# FlatSat_Final.net
KiCad netlist of a schematic drawn in EAGLE
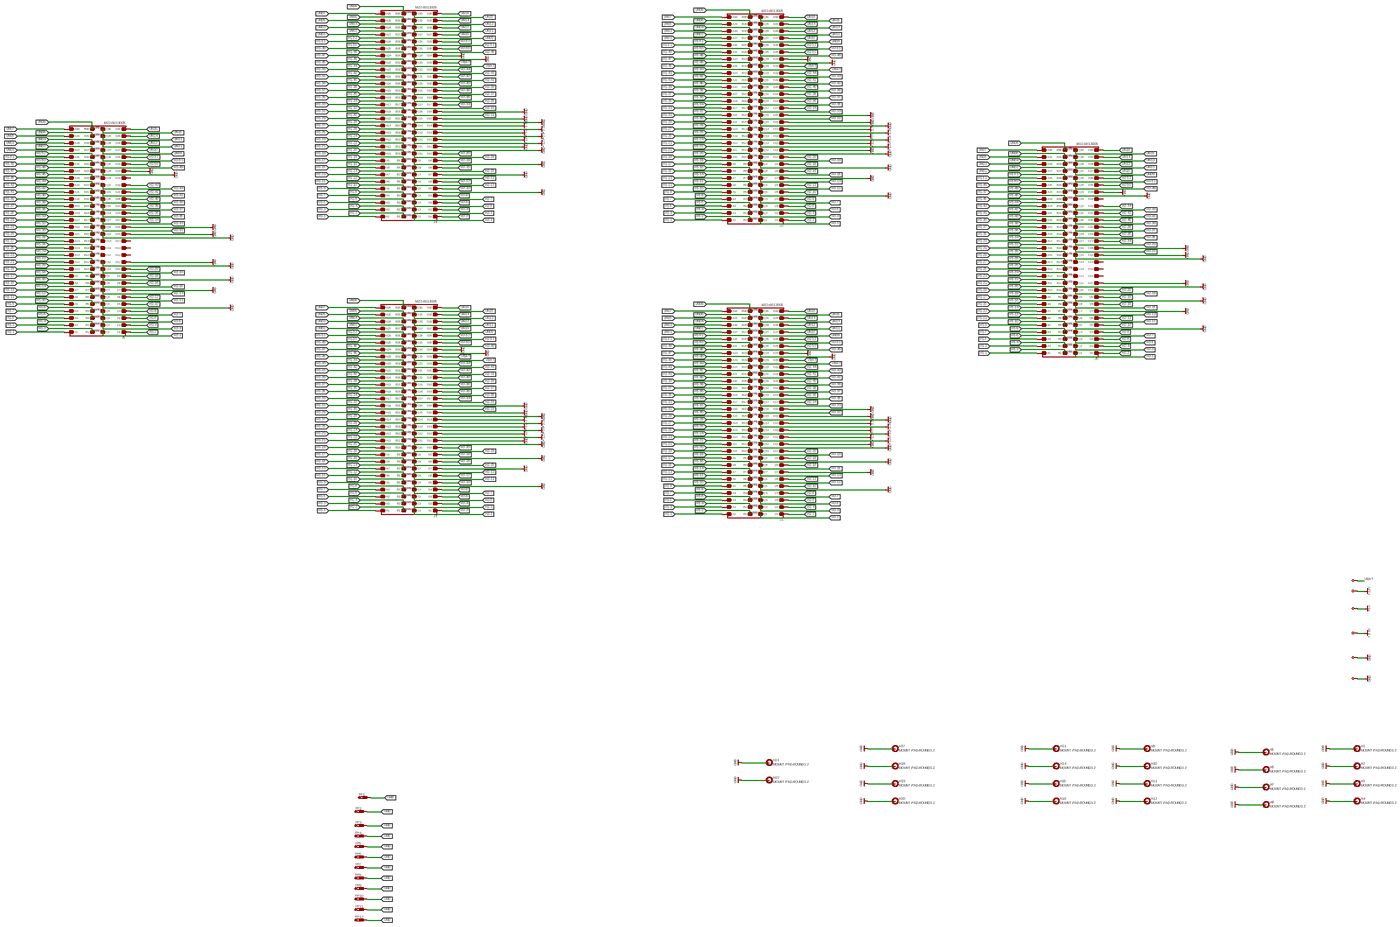
[diagram p0: schematic, sheet 1, overview]
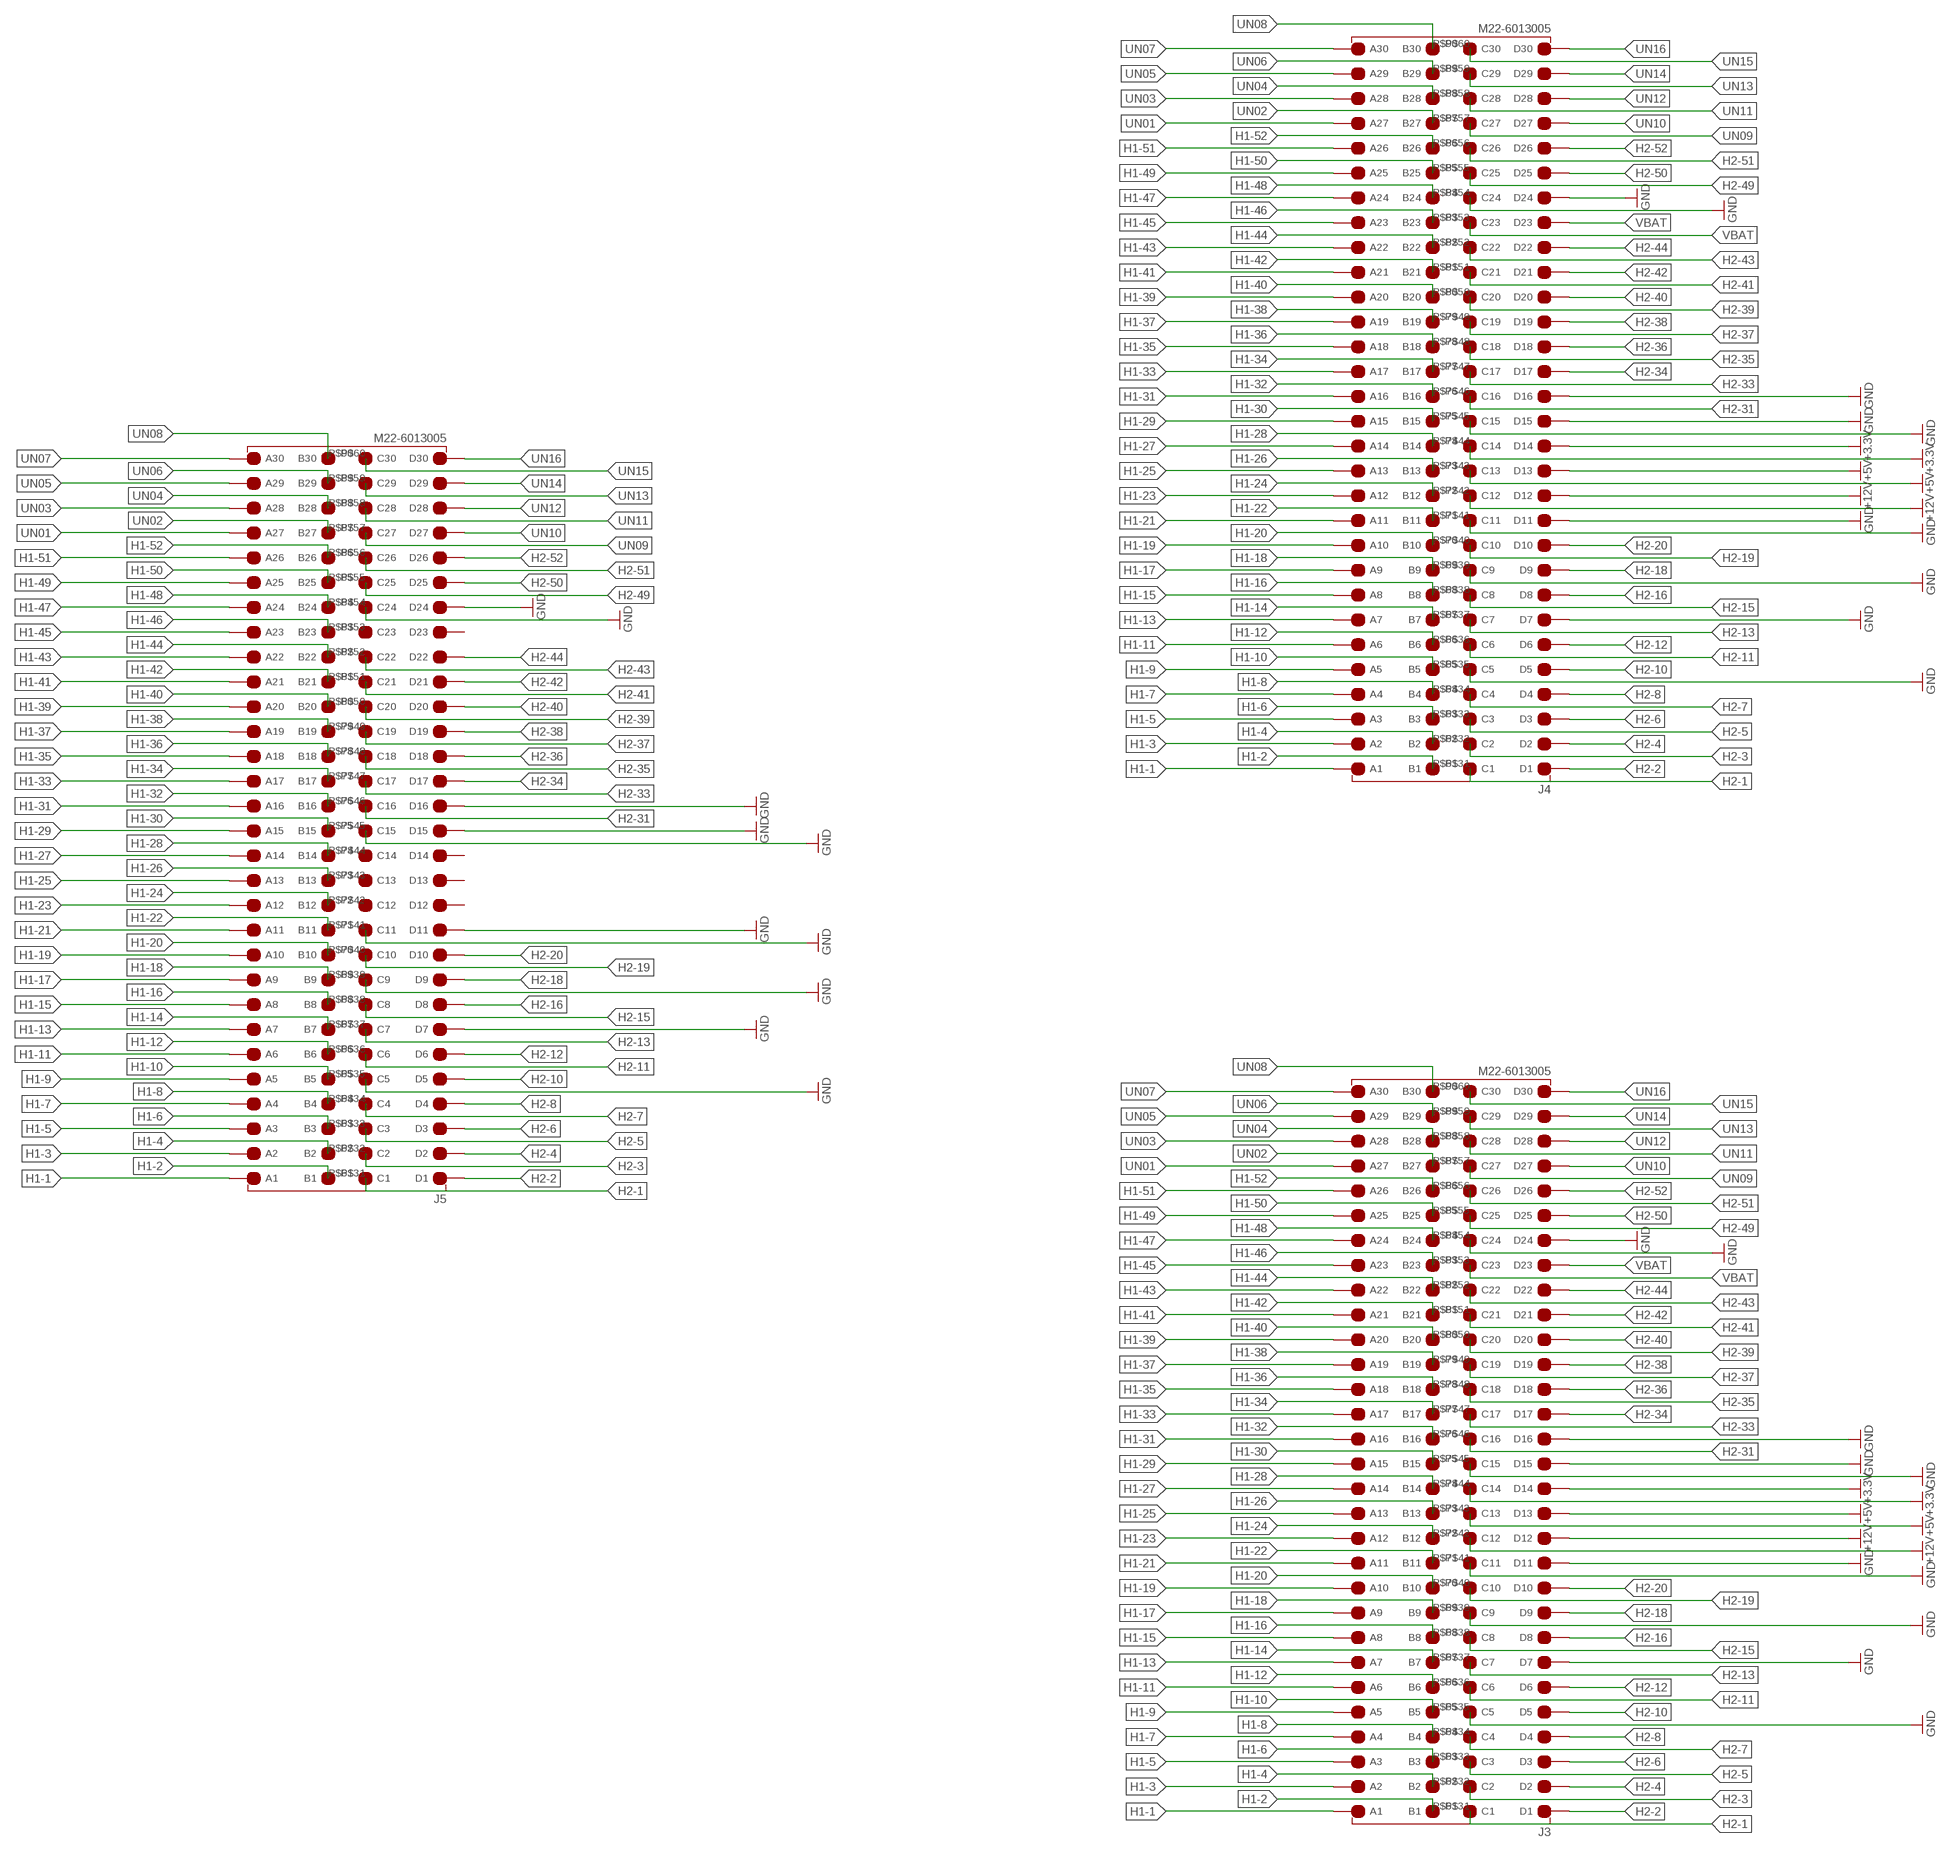
[diagram p1: schematic, sheet 1, part 1 of 5]
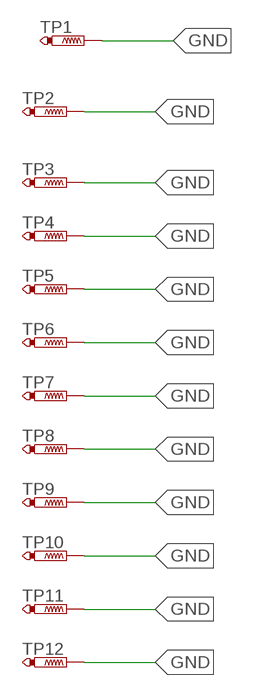
[diagram p2: schematic, sheet 1, part 2 of 5]
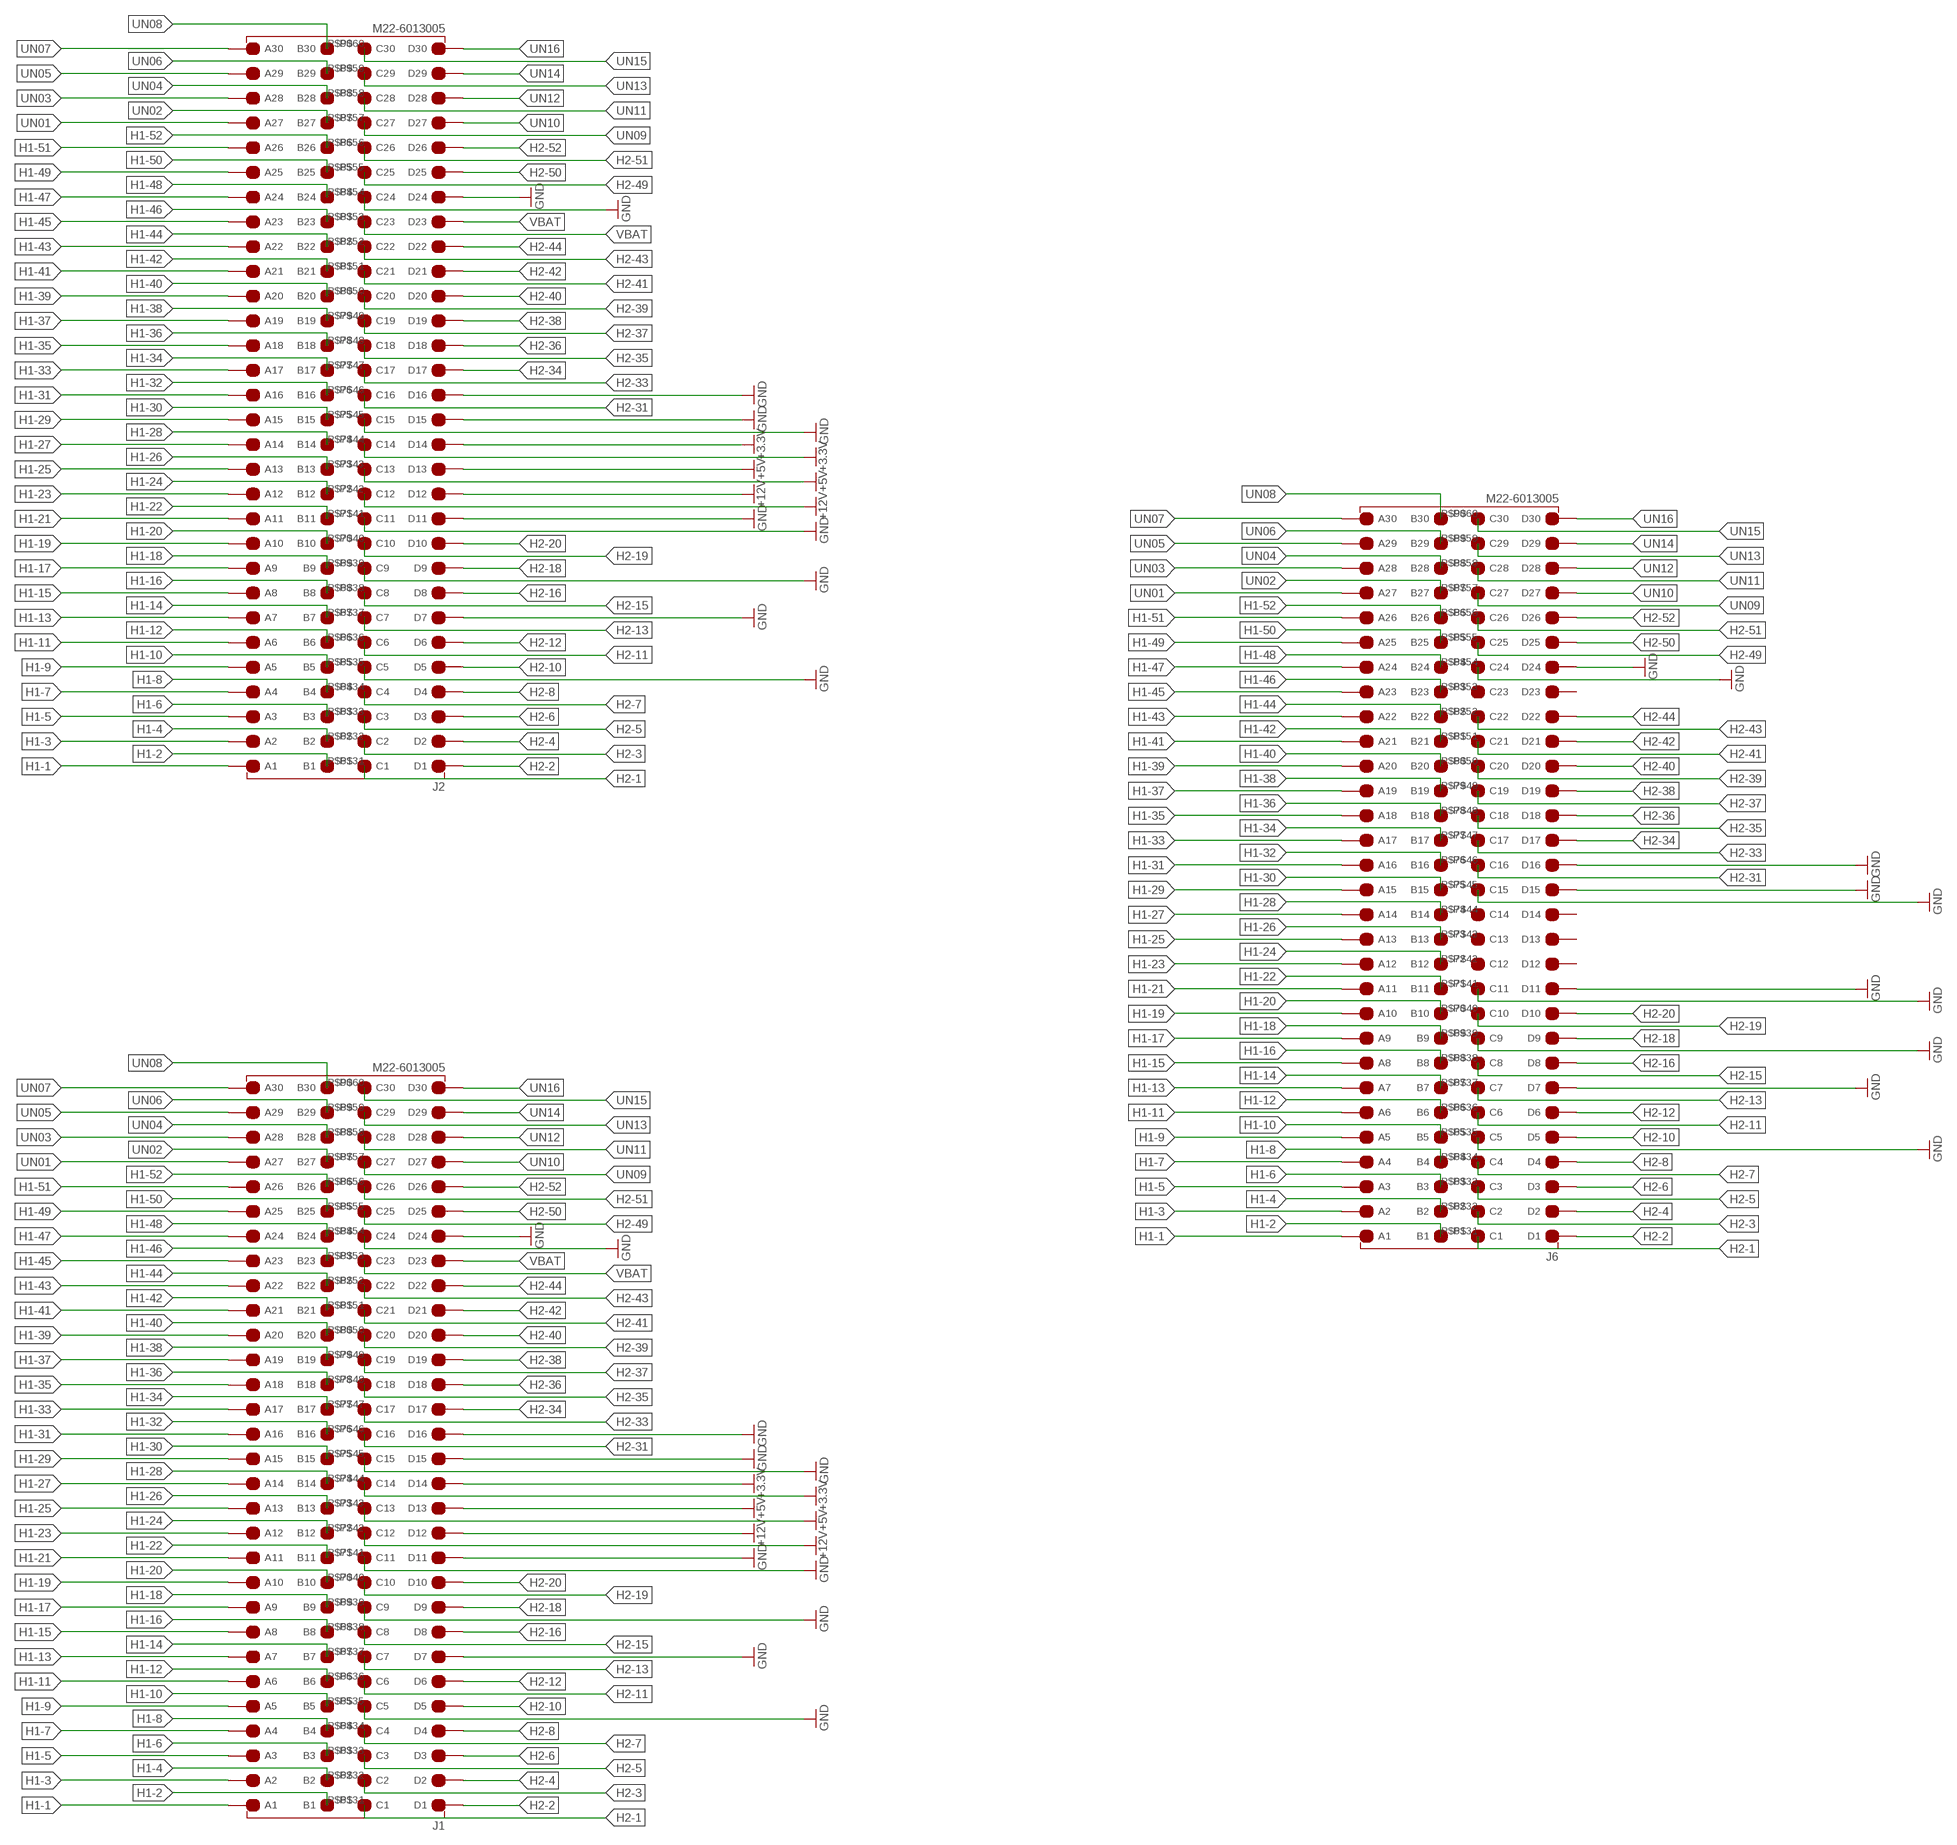
[diagram p3: schematic, sheet 1, part 3 of 5]
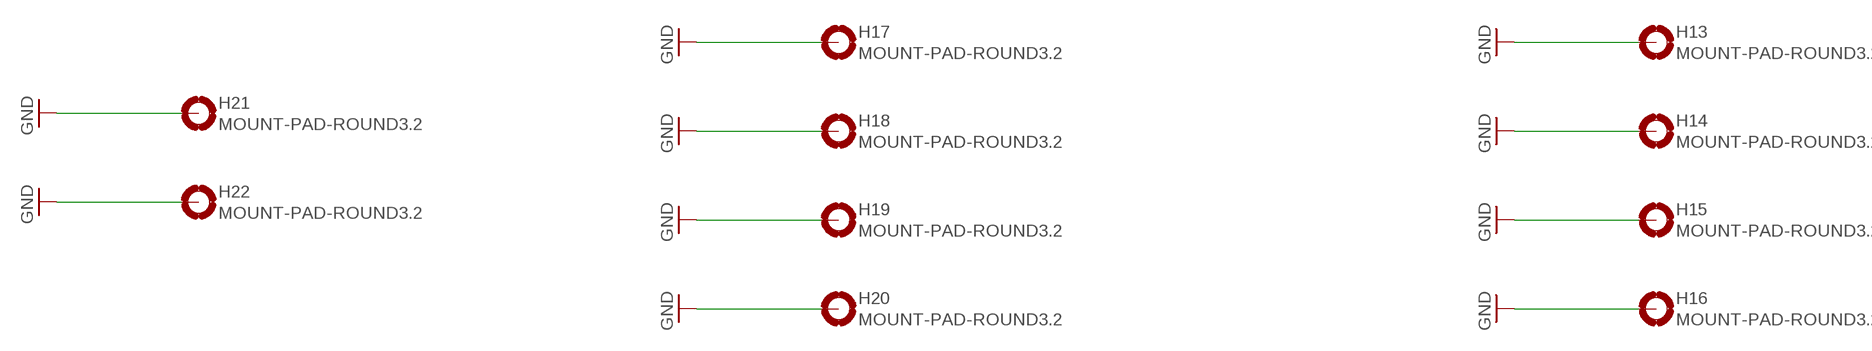
[diagram p4: schematic, sheet 1, part 4 of 5]
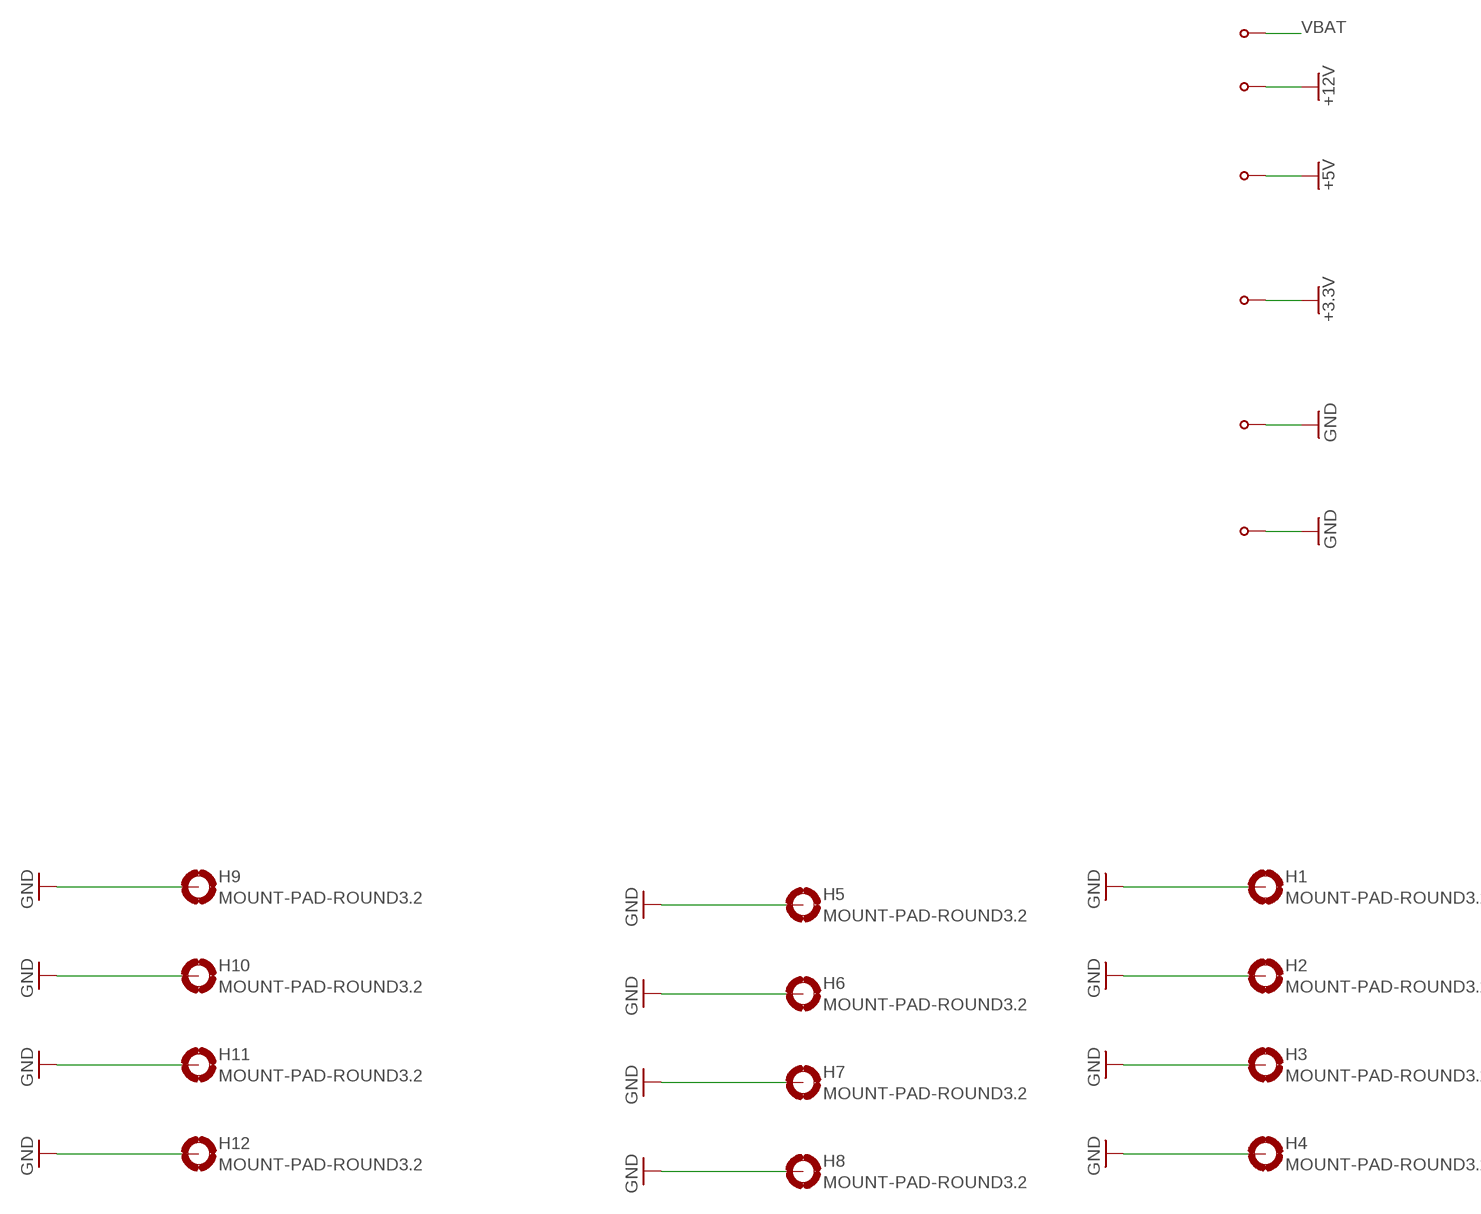
[diagram p5: schematic, sheet 1, part 5 of 5]

(export (version "E")
  (design (tool "Eeschema 10.0.6"))
  (components
    (comp (ref "H1")
      (value "MOUNT-PAD-ROUND3.2")
      (footprint "eagle-import:3,2-PAD")
      (libsource (lib "eagle-import") (part "MOUNT-PAD-ROUND3.2"))
    )
    (comp (ref "H2")
      (value "MOUNT-PAD-ROUND3.2")
      (footprint "eagle-import:3,2-PAD")
      (libsource (lib "eagle-import") (part "MOUNT-PAD-ROUND3.2"))
    )
    (comp (ref "H3")
      (value "MOUNT-PAD-ROUND3.2")
      (footprint "eagle-import:3,2-PAD")
      (libsource (lib "eagle-import") (part "MOUNT-PAD-ROUND3.2"))
    )
    (comp (ref "H4")
      (value "MOUNT-PAD-ROUND3.2")
      (footprint "eagle-import:3,2-PAD")
      (libsource (lib "eagle-import") (part "MOUNT-PAD-ROUND3.2"))
    )
    (comp (ref "H5")
      (value "MOUNT-PAD-ROUND3.2")
      (footprint "eagle-import:3,2-PAD")
      (libsource (lib "eagle-import") (part "MOUNT-PAD-ROUND3.2"))
    )
    (comp (ref "H6")
      (value "MOUNT-PAD-ROUND3.2")
      (footprint "eagle-import:3,2-PAD")
      (libsource (lib "eagle-import") (part "MOUNT-PAD-ROUND3.2"))
    )
    (comp (ref "H7")
      (value "MOUNT-PAD-ROUND3.2")
      (footprint "eagle-import:3,2-PAD")
      (libsource (lib "eagle-import") (part "MOUNT-PAD-ROUND3.2"))
    )
    (comp (ref "H8")
      (value "MOUNT-PAD-ROUND3.2")
      (footprint "eagle-import:3,2-PAD")
      (libsource (lib "eagle-import") (part "MOUNT-PAD-ROUND3.2"))
    )
    (comp (ref "H9")
      (value "MOUNT-PAD-ROUND3.2")
      (footprint "eagle-import:3,2-PAD")
      (libsource (lib "eagle-import") (part "MOUNT-PAD-ROUND3.2"))
    )
    (comp (ref "H10")
      (value "MOUNT-PAD-ROUND3.2")
      (footprint "eagle-import:3,2-PAD")
      (libsource (lib "eagle-import") (part "MOUNT-PAD-ROUND3.2"))
    )
    (comp (ref "H11")
      (value "MOUNT-PAD-ROUND3.2")
      (footprint "eagle-import:3,2-PAD")
      (libsource (lib "eagle-import") (part "MOUNT-PAD-ROUND3.2"))
    )
    (comp (ref "H12")
      (value "MOUNT-PAD-ROUND3.2")
      (footprint "eagle-import:3,2-PAD")
      (libsource (lib "eagle-import") (part "MOUNT-PAD-ROUND3.2"))
    )
    (comp (ref "H13")
      (value "MOUNT-PAD-ROUND3.2")
      (footprint "eagle-import:3,2-PAD")
      (libsource (lib "eagle-import") (part "MOUNT-PAD-ROUND3.2"))
    )
    (comp (ref "H14")
      (value "MOUNT-PAD-ROUND3.2")
      (footprint "eagle-import:3,2-PAD")
      (libsource (lib "eagle-import") (part "MOUNT-PAD-ROUND3.2"))
    )
    (comp (ref "H15")
      (value "MOUNT-PAD-ROUND3.2")
      (footprint "eagle-import:3,2-PAD")
      (libsource (lib "eagle-import") (part "MOUNT-PAD-ROUND3.2"))
    )
    (comp (ref "H16")
      (value "MOUNT-PAD-ROUND3.2")
      (footprint "eagle-import:3,2-PAD")
      (libsource (lib "eagle-import") (part "MOUNT-PAD-ROUND3.2"))
    )
    (comp (ref "H17")
      (value "MOUNT-PAD-ROUND3.2")
      (footprint "eagle-import:3,2-PAD")
      (libsource (lib "eagle-import") (part "MOUNT-PAD-ROUND3.2"))
    )
    (comp (ref "H18")
      (value "MOUNT-PAD-ROUND3.2")
      (footprint "eagle-import:3,2-PAD")
      (libsource (lib "eagle-import") (part "MOUNT-PAD-ROUND3.2"))
    )
    (comp (ref "H19")
      (value "MOUNT-PAD-ROUND3.2")
      (footprint "eagle-import:3,2-PAD")
      (libsource (lib "eagle-import") (part "MOUNT-PAD-ROUND3.2"))
    )
    (comp (ref "H20")
      (value "MOUNT-PAD-ROUND3.2")
      (footprint "eagle-import:3,2-PAD")
      (libsource (lib "eagle-import") (part "MOUNT-PAD-ROUND3.2"))
    )
    (comp (ref "H21")
      (value "MOUNT-PAD-ROUND3.2")
      (footprint "eagle-import:3,2-PAD")
      (libsource (lib "eagle-import") (part "MOUNT-PAD-ROUND3.2"))
    )
    (comp (ref "H22")
      (value "MOUNT-PAD-ROUND3.2")
      (footprint "eagle-import:3,2-PAD")
      (libsource (lib "eagle-import") (part "MOUNT-PAD-ROUND3.2"))
    )
    (comp (ref "J1")
      (value "M22-6013005")
      (footprint "eagle-import:RHDR120W55P200_4X30_6020X820X9")
      (libsource (lib "eagle-import") (part "M22-6013005"))
    )
    (comp (ref "J2")
      (value "M22-6013005")
      (footprint "eagle-import:RHDR120W55P200_4X30_6020X820X9")
      (libsource (lib "eagle-import") (part "M22-6013005"))
    )
    (comp (ref "J3")
      (value "M22-6013005")
      (footprint "eagle-import:RHDR120W55P200_4X30_6020X820X9")
      (libsource (lib "eagle-import") (part "M22-6013005"))
    )
    (comp (ref "J4")
      (value "M22-6013005")
      (footprint "eagle-import:RHDR120W55P200_4X30_6020X820X9")
      (libsource (lib "eagle-import") (part "M22-6013005"))
    )
    (comp (ref "J5")
      (value "M22-6013005")
      (footprint "eagle-import:RHDR120W55P200_4X30_6020X820X9")
      (libsource (lib "eagle-import") (part "M22-6013005"))
    )
    (comp (ref "J6")
      (value "M22-6013005")
      (footprint "eagle-import:RHDR120W55P200_4X30_6020X820X9")
      (libsource (lib "eagle-import") (part "M22-6013005"))
    )
    (comp (ref "TP1")
      (value "PTR1PAD1-13")
      (footprint "eagle-import:P1-13")
      (libsource (lib "eagle-import") (part "PTR1PAD1-13"))
    )
    (comp (ref "TP2")
      (value "PTR1PAD1-13")
      (footprint "eagle-import:P1-13")
      (libsource (lib "eagle-import") (part "PTR1PAD1-13"))
    )
    (comp (ref "TP3")
      (value "PTR1PAD1-13")
      (footprint "eagle-import:P1-13")
      (libsource (lib "eagle-import") (part "PTR1PAD1-13"))
    )
    (comp (ref "TP4")
      (value "PTR1PAD1-13")
      (footprint "eagle-import:P1-13")
      (libsource (lib "eagle-import") (part "PTR1PAD1-13"))
    )
    (comp (ref "TP5")
      (value "PTR1PAD1-13")
      (footprint "eagle-import:P1-13")
      (libsource (lib "eagle-import") (part "PTR1PAD1-13"))
    )
    (comp (ref "TP6")
      (value "PTR1PAD1-13")
      (footprint "eagle-import:P1-13")
      (libsource (lib "eagle-import") (part "PTR1PAD1-13"))
    )
    (comp (ref "TP7")
      (value "PTR1PAD1-13")
      (footprint "eagle-import:P1-13")
      (libsource (lib "eagle-import") (part "PTR1PAD1-13"))
    )
    (comp (ref "TP8")
      (value "PTR1PAD1-13")
      (footprint "eagle-import:P1-13")
      (libsource (lib "eagle-import") (part "PTR1PAD1-13"))
    )
    (comp (ref "TP9")
      (value "PTR1PAD1-13")
      (footprint "eagle-import:P1-13")
      (libsource (lib "eagle-import") (part "PTR1PAD1-13"))
    )
    (comp (ref "TP10")
      (value "PTR1PAD1-13")
      (footprint "eagle-import:P1-13")
      (libsource (lib "eagle-import") (part "PTR1PAD1-13"))
    )
    (comp (ref "TP11")
      (value "PTR1PAD1-13")
      (footprint "eagle-import:P1-13")
      (libsource (lib "eagle-import") (part "PTR1PAD1-13"))
    )
    (comp (ref "TP12")
      (value "PTR1PAD1-13")
      (footprint "eagle-import:P1-13")
      (libsource (lib "eagle-import") (part "PTR1PAD1-13"))
    )
    (comp (ref "U$1")
      (value "BANANA-JACK")
      (footprint "eagle-import:BANANA-PRINT")
      (libsource (lib "eagle-import") (part "BANANA-JACK"))
    )
    (comp (ref "U$2")
      (value "BANANA-JACK")
      (footprint "eagle-import:BANANA-PRINT")
      (libsource (lib "eagle-import") (part "BANANA-JACK"))
    )
    (comp (ref "U$3")
      (value "BANANA-JACK")
      (footprint "eagle-import:BANANA-PRINT")
      (libsource (lib "eagle-import") (part "BANANA-JACK"))
    )
    (comp (ref "U$4")
      (value "BANANA-JACK")
      (footprint "eagle-import:BANANA-PRINT")
      (libsource (lib "eagle-import") (part "BANANA-JACK"))
    )
    (comp (ref "U$5")
      (value "BANANA-JACK")
      (footprint "eagle-import:BANANA-PRINT")
      (libsource (lib "eagle-import") (part "BANANA-JACK"))
    )
    (comp (ref "U$6")
      (value "BANANA-JACK")
      (footprint "eagle-import:BANANA-PRINT")
      (libsource (lib "eagle-import") (part "BANANA-JACK"))
    )
  )
  (nets
    (net (code "1") (name "+3.3V") (class "Default")
      (node (ref "J1") (pin "P$14") (pinfunction "D14_P$14") (pintype "passive"))
      (node (ref "J1") (pin "P$44") (pinfunction "C14_P$44") (pintype "passive"))
      (node (ref "J2") (pin "P$14") (pinfunction "D14_P$14") (pintype "passive"))
      (node (ref "J2") (pin "P$44") (pinfunction "C14_P$44") (pintype "passive"))
      (node (ref "J3") (pin "P$14") (pinfunction "D14_P$14") (pintype "passive"))
      (node (ref "J3") (pin "P$44") (pinfunction "C14_P$44") (pintype "passive"))
      (node (ref "J4") (pin "P$14") (pinfunction "D14_P$14") (pintype "passive"))
      (node (ref "J4") (pin "P$44") (pinfunction "C14_P$44") (pintype "passive"))
      (node (ref "U$3") (pin "P$1") (pinfunction "PIN_P$1") (pintype "bidirectional"))
    )
    (net (code "2") (name "+5V") (class "Default")
      (node (ref "J1") (pin "P$13") (pinfunction "D13_P$13") (pintype "passive"))
      (node (ref "J1") (pin "P$43") (pinfunction "C13_P$43") (pintype "passive"))
      (node (ref "J2") (pin "P$13") (pinfunction "D13_P$13") (pintype "passive"))
      (node (ref "J2") (pin "P$43") (pinfunction "C13_P$43") (pintype "passive"))
      (node (ref "J3") (pin "P$13") (pinfunction "D13_P$13") (pintype "passive"))
      (node (ref "J3") (pin "P$43") (pinfunction "C13_P$43") (pintype "passive"))
      (node (ref "J4") (pin "P$13") (pinfunction "D13_P$13") (pintype "passive"))
      (node (ref "J4") (pin "P$43") (pinfunction "C13_P$43") (pintype "passive"))
      (node (ref "U$2") (pin "P$1") (pinfunction "PIN_P$1") (pintype "bidirectional"))
    )
    (net (code "3") (name "+12V") (class "Default")
      (node (ref "J1") (pin "P$12") (pinfunction "D12_P$12") (pintype "passive"))
      (node (ref "J1") (pin "P$42") (pinfunction "C12_P$42") (pintype "passive"))
      (node (ref "J2") (pin "P$12") (pinfunction "D12_P$12") (pintype "passive"))
      (node (ref "J2") (pin "P$42") (pinfunction "C12_P$42") (pintype "passive"))
      (node (ref "J3") (pin "P$12") (pinfunction "D12_P$12") (pintype "passive"))
      (node (ref "J3") (pin "P$42") (pinfunction "C12_P$42") (pintype "passive"))
      (node (ref "J4") (pin "P$12") (pinfunction "D12_P$12") (pintype "passive"))
      (node (ref "J4") (pin "P$42") (pinfunction "C12_P$42") (pintype "passive"))
      (node (ref "U$1") (pin "P$1") (pinfunction "PIN_P$1") (pintype "bidirectional"))
    )
    (net (code "4") (name "GND") (class "Default")
      (node (ref "H1") (pin "B3,2") (pinfunction "MOUNT_B3,2") (pintype "passive"))
      (node (ref "H10") (pin "B3,2") (pinfunction "MOUNT_B3,2") (pintype "passive"))
      (node (ref "H11") (pin "B3,2") (pinfunction "MOUNT_B3,2") (pintype "passive"))
      (node (ref "H12") (pin "B3,2") (pinfunction "MOUNT_B3,2") (pintype "passive"))
      (node (ref "H13") (pin "B3,2") (pinfunction "MOUNT_B3,2") (pintype "passive"))
      (node (ref "H14") (pin "B3,2") (pinfunction "MOUNT_B3,2") (pintype "passive"))
      (node (ref "H15") (pin "B3,2") (pinfunction "MOUNT_B3,2") (pintype "passive"))
      (node (ref "H16") (pin "B3,2") (pinfunction "MOUNT_B3,2") (pintype "passive"))
      (node (ref "H17") (pin "B3,2") (pinfunction "MOUNT_B3,2") (pintype "passive"))
      (node (ref "H18") (pin "B3,2") (pinfunction "MOUNT_B3,2") (pintype "passive"))
      (node (ref "H19") (pin "B3,2") (pinfunction "MOUNT_B3,2") (pintype "passive"))
      (node (ref "H2") (pin "B3,2") (pinfunction "MOUNT_B3,2") (pintype "passive"))
      (node (ref "H20") (pin "B3,2") (pinfunction "MOUNT_B3,2") (pintype "passive"))
      (node (ref "H21") (pin "B3,2") (pinfunction "MOUNT_B3,2") (pintype "passive"))
      (node (ref "H22") (pin "B3,2") (pinfunction "MOUNT_B3,2") (pintype "passive"))
      (node (ref "H3") (pin "B3,2") (pinfunction "MOUNT_B3,2") (pintype "passive"))
      (node (ref "H4") (pin "B3,2") (pinfunction "MOUNT_B3,2") (pintype "passive"))
      (node (ref "H5") (pin "B3,2") (pinfunction "MOUNT_B3,2") (pintype "passive"))
      (node (ref "H6") (pin "B3,2") (pinfunction "MOUNT_B3,2") (pintype "passive"))
      (node (ref "H7") (pin "B3,2") (pinfunction "MOUNT_B3,2") (pintype "passive"))
      (node (ref "H8") (pin "B3,2") (pinfunction "MOUNT_B3,2") (pintype "passive"))
      (node (ref "H9") (pin "B3,2") (pinfunction "MOUNT_B3,2") (pintype "passive"))
      (node (ref "J1") (pin "P$11") (pinfunction "D11_P$11") (pintype "passive"))
      (node (ref "J1") (pin "P$15") (pinfunction "D15_P$15") (pintype "passive"))
      (node (ref "J1") (pin "P$16") (pinfunction "D16_P$16") (pintype "passive"))
      (node (ref "J1") (pin "P$24") (pinfunction "D24_P$24") (pintype "passive"))
      (node (ref "J1") (pin "P$35") (pinfunction "C5_P$35") (pintype "passive"))
      (node (ref "J1") (pin "P$39") (pinfunction "C9_P$39") (pintype "passive"))
      (node (ref "J1") (pin "P$41") (pinfunction "C11_P$41") (pintype "passive"))
      (node (ref "J1") (pin "P$45") (pinfunction "C15_P$45") (pintype "passive"))
      (node (ref "J1") (pin "P$54") (pinfunction "C24_P$54") (pintype "passive"))
      (node (ref "J1") (pin "P$7") (pinfunction "D7_P$7") (pintype "passive"))
      (node (ref "J2") (pin "P$11") (pinfunction "D11_P$11") (pintype "passive"))
      (node (ref "J2") (pin "P$15") (pinfunction "D15_P$15") (pintype "passive"))
      (node (ref "J2") (pin "P$16") (pinfunction "D16_P$16") (pintype "passive"))
      (node (ref "J2") (pin "P$24") (pinfunction "D24_P$24") (pintype "passive"))
      (node (ref "J2") (pin "P$35") (pinfunction "C5_P$35") (pintype "passive"))
      (node (ref "J2") (pin "P$39") (pinfunction "C9_P$39") (pintype "passive"))
      (node (ref "J2") (pin "P$41") (pinfunction "C11_P$41") (pintype "passive"))
      (node (ref "J2") (pin "P$45") (pinfunction "C15_P$45") (pintype "passive"))
      (node (ref "J2") (pin "P$54") (pinfunction "C24_P$54") (pintype "passive"))
      (node (ref "J2") (pin "P$7") (pinfunction "D7_P$7") (pintype "passive"))
      (node (ref "J3") (pin "P$11") (pinfunction "D11_P$11") (pintype "passive"))
      (node (ref "J3") (pin "P$15") (pinfunction "D15_P$15") (pintype "passive"))
      (node (ref "J3") (pin "P$16") (pinfunction "D16_P$16") (pintype "passive"))
      (node (ref "J3") (pin "P$24") (pinfunction "D24_P$24") (pintype "passive"))
      (node (ref "J3") (pin "P$35") (pinfunction "C5_P$35") (pintype "passive"))
      (node (ref "J3") (pin "P$39") (pinfunction "C9_P$39") (pintype "passive"))
      (node (ref "J3") (pin "P$41") (pinfunction "C11_P$41") (pintype "passive"))
      (node (ref "J3") (pin "P$45") (pinfunction "C15_P$45") (pintype "passive"))
      (node (ref "J3") (pin "P$54") (pinfunction "C24_P$54") (pintype "passive"))
      (node (ref "J3") (pin "P$7") (pinfunction "D7_P$7") (pintype "passive"))
      (node (ref "J4") (pin "P$11") (pinfunction "D11_P$11") (pintype "passive"))
      (node (ref "J4") (pin "P$15") (pinfunction "D15_P$15") (pintype "passive"))
      (node (ref "J4") (pin "P$16") (pinfunction "D16_P$16") (pintype "passive"))
      (node (ref "J4") (pin "P$24") (pinfunction "D24_P$24") (pintype "passive"))
      (node (ref "J4") (pin "P$35") (pinfunction "C5_P$35") (pintype "passive"))
      (node (ref "J4") (pin "P$39") (pinfunction "C9_P$39") (pintype "passive"))
      (node (ref "J4") (pin "P$41") (pinfunction "C11_P$41") (pintype "passive"))
      (node (ref "J4") (pin "P$45") (pinfunction "C15_P$45") (pintype "passive"))
      (node (ref "J4") (pin "P$54") (pinfunction "C24_P$54") (pintype "passive"))
      (node (ref "J4") (pin "P$7") (pinfunction "D7_P$7") (pintype "passive"))
      (node (ref "J5") (pin "P$11") (pinfunction "D11_P$11") (pintype "passive"))
      (node (ref "J5") (pin "P$15") (pinfunction "D15_P$15") (pintype "passive"))
      (node (ref "J5") (pin "P$16") (pinfunction "D16_P$16") (pintype "passive"))
      (node (ref "J5") (pin "P$24") (pinfunction "D24_P$24") (pintype "passive"))
      (node (ref "J5") (pin "P$35") (pinfunction "C5_P$35") (pintype "passive"))
      (node (ref "J5") (pin "P$39") (pinfunction "C9_P$39") (pintype "passive"))
      (node (ref "J5") (pin "P$41") (pinfunction "C11_P$41") (pintype "passive"))
      (node (ref "J5") (pin "P$45") (pinfunction "C15_P$45") (pintype "passive"))
      (node (ref "J5") (pin "P$54") (pinfunction "C24_P$54") (pintype "passive"))
      (node (ref "J5") (pin "P$7") (pinfunction "D7_P$7") (pintype "passive"))
      (node (ref "J6") (pin "P$11") (pinfunction "D11_P$11") (pintype "passive"))
      (node (ref "J6") (pin "P$15") (pinfunction "D15_P$15") (pintype "passive"))
      (node (ref "J6") (pin "P$16") (pinfunction "D16_P$16") (pintype "passive"))
      (node (ref "J6") (pin "P$24") (pinfunction "D24_P$24") (pintype "passive"))
      (node (ref "J6") (pin "P$35") (pinfunction "C5_P$35") (pintype "passive"))
      (node (ref "J6") (pin "P$39") (pinfunction "C9_P$39") (pintype "passive"))
      (node (ref "J6") (pin "P$41") (pinfunction "C11_P$41") (pintype "passive"))
      (node (ref "J6") (pin "P$45") (pinfunction "C15_P$45") (pintype "passive"))
      (node (ref "J6") (pin "P$54") (pinfunction "C24_P$54") (pintype "passive"))
      (node (ref "J6") (pin "P$7") (pinfunction "D7_P$7") (pintype "passive"))
      (node (ref "TP1") (pin "TP") (pinfunction "TP_TP") (pintype "input"))
      (node (ref "TP10") (pin "TP") (pinfunction "TP_TP") (pintype "input"))
      (node (ref "TP11") (pin "TP") (pinfunction "TP_TP") (pintype "input"))
      (node (ref "TP12") (pin "TP") (pinfunction "TP_TP") (pintype "input"))
      (node (ref "TP2") (pin "TP") (pinfunction "TP_TP") (pintype "input"))
      (node (ref "TP3") (pin "TP") (pinfunction "TP_TP") (pintype "input"))
      (node (ref "TP4") (pin "TP") (pinfunction "TP_TP") (pintype "input"))
      (node (ref "TP5") (pin "TP") (pinfunction "TP_TP") (pintype "input"))
      (node (ref "TP6") (pin "TP") (pinfunction "TP_TP") (pintype "input"))
      (node (ref "TP7") (pin "TP") (pinfunction "TP_TP") (pintype "input"))
      (node (ref "TP8") (pin "TP") (pinfunction "TP_TP") (pintype "input"))
      (node (ref "TP9") (pin "TP") (pinfunction "TP_TP") (pintype "input"))
      (node (ref "U$4") (pin "P$1") (pinfunction "PIN_P$1") (pintype "bidirectional"))
      (node (ref "U$5") (pin "P$1") (pinfunction "PIN_P$1") (pintype "bidirectional"))
    )
    (net (code "5") (name "H1-1") (class "Default")
      (node (ref "J1") (pin "P$91") (pinfunction "A1_P$91") (pintype "passive"))
      (node (ref "J2") (pin "P$91") (pinfunction "A1_P$91") (pintype "passive"))
      (node (ref "J3") (pin "P$91") (pinfunction "A1_P$91") (pintype "passive"))
      (node (ref "J4") (pin "P$91") (pinfunction "A1_P$91") (pintype "passive"))
      (node (ref "J5") (pin "P$91") (pinfunction "A1_P$91") (pintype "passive"))
      (node (ref "J6") (pin "P$91") (pinfunction "A1_P$91") (pintype "passive"))
    )
    (net (code "6") (name "H1-2") (class "Default")
      (node (ref "J1") (pin "P$61") (pinfunction "B1_P$61") (pintype "passive"))
      (node (ref "J2") (pin "P$61") (pinfunction "B1_P$61") (pintype "passive"))
      (node (ref "J3") (pin "P$61") (pinfunction "B1_P$61") (pintype "passive"))
      (node (ref "J4") (pin "P$61") (pinfunction "B1_P$61") (pintype "passive"))
      (node (ref "J5") (pin "P$61") (pinfunction "B1_P$61") (pintype "passive"))
      (node (ref "J6") (pin "P$61") (pinfunction "B1_P$61") (pintype "passive"))
    )
    (net (code "7") (name "H1-3") (class "Default")
      (node (ref "J1") (pin "P$92") (pinfunction "A2_P$92") (pintype "passive"))
      (node (ref "J2") (pin "P$92") (pinfunction "A2_P$92") (pintype "passive"))
      (node (ref "J3") (pin "P$92") (pinfunction "A2_P$92") (pintype "passive"))
      (node (ref "J4") (pin "P$92") (pinfunction "A2_P$92") (pintype "passive"))
      (node (ref "J5") (pin "P$92") (pinfunction "A2_P$92") (pintype "passive"))
      (node (ref "J6") (pin "P$92") (pinfunction "A2_P$92") (pintype "passive"))
    )
    (net (code "8") (name "H1-4") (class "Default")
      (node (ref "J1") (pin "P$62") (pinfunction "B2_P$62") (pintype "passive"))
      (node (ref "J2") (pin "P$62") (pinfunction "B2_P$62") (pintype "passive"))
      (node (ref "J3") (pin "P$62") (pinfunction "B2_P$62") (pintype "passive"))
      (node (ref "J4") (pin "P$62") (pinfunction "B2_P$62") (pintype "passive"))
      (node (ref "J5") (pin "P$62") (pinfunction "B2_P$62") (pintype "passive"))
      (node (ref "J6") (pin "P$62") (pinfunction "B2_P$62") (pintype "passive"))
    )
    (net (code "9") (name "H1-5") (class "Default")
      (node (ref "J1") (pin "P$93") (pinfunction "A3_P$93") (pintype "passive"))
      (node (ref "J2") (pin "P$93") (pinfunction "A3_P$93") (pintype "passive"))
      (node (ref "J3") (pin "P$93") (pinfunction "A3_P$93") (pintype "passive"))
      (node (ref "J4") (pin "P$93") (pinfunction "A3_P$93") (pintype "passive"))
      (node (ref "J5") (pin "P$93") (pinfunction "A3_P$93") (pintype "passive"))
      (node (ref "J6") (pin "P$93") (pinfunction "A3_P$93") (pintype "passive"))
    )
    (net (code "10") (name "H1-6") (class "Default")
      (node (ref "J1") (pin "P$63") (pinfunction "B3_P$63") (pintype "passive"))
      (node (ref "J2") (pin "P$63") (pinfunction "B3_P$63") (pintype "passive"))
      (node (ref "J3") (pin "P$63") (pinfunction "B3_P$63") (pintype "passive"))
      (node (ref "J4") (pin "P$63") (pinfunction "B3_P$63") (pintype "passive"))
      (node (ref "J5") (pin "P$63") (pinfunction "B3_P$63") (pintype "passive"))
      (node (ref "J6") (pin "P$63") (pinfunction "B3_P$63") (pintype "passive"))
    )
    (net (code "11") (name "H1-7") (class "Default")
      (node (ref "J1") (pin "P$94") (pinfunction "A4_P$94") (pintype "passive"))
      (node (ref "J2") (pin "P$94") (pinfunction "A4_P$94") (pintype "passive"))
      (node (ref "J3") (pin "P$94") (pinfunction "A4_P$94") (pintype "passive"))
      (node (ref "J4") (pin "P$94") (pinfunction "A4_P$94") (pintype "passive"))
      (node (ref "J5") (pin "P$94") (pinfunction "A4_P$94") (pintype "passive"))
      (node (ref "J6") (pin "P$94") (pinfunction "A4_P$94") (pintype "passive"))
    )
    (net (code "12") (name "H1-8") (class "Default")
      (node (ref "J1") (pin "P$64") (pinfunction "B4_P$64") (pintype "passive"))
      (node (ref "J2") (pin "P$64") (pinfunction "B4_P$64") (pintype "passive"))
      (node (ref "J3") (pin "P$64") (pinfunction "B4_P$64") (pintype "passive"))
      (node (ref "J4") (pin "P$64") (pinfunction "B4_P$64") (pintype "passive"))
      (node (ref "J5") (pin "P$64") (pinfunction "B4_P$64") (pintype "passive"))
      (node (ref "J6") (pin "P$64") (pinfunction "B4_P$64") (pintype "passive"))
    )
    (net (code "13") (name "H1-9") (class "Default")
      (node (ref "J1") (pin "P$95") (pinfunction "A5_P$95") (pintype "passive"))
      (node (ref "J2") (pin "P$95") (pinfunction "A5_P$95") (pintype "passive"))
      (node (ref "J3") (pin "P$95") (pinfunction "A5_P$95") (pintype "passive"))
      (node (ref "J4") (pin "P$95") (pinfunction "A5_P$95") (pintype "passive"))
      (node (ref "J5") (pin "P$95") (pinfunction "A5_P$95") (pintype "passive"))
      (node (ref "J6") (pin "P$95") (pinfunction "A5_P$95") (pintype "passive"))
    )
    (net (code "14") (name "H1-10") (class "Default")
      (node (ref "J1") (pin "P$65") (pinfunction "B5_P$65") (pintype "passive"))
      (node (ref "J2") (pin "P$65") (pinfunction "B5_P$65") (pintype "passive"))
      (node (ref "J3") (pin "P$65") (pinfunction "B5_P$65") (pintype "passive"))
      (node (ref "J4") (pin "P$65") (pinfunction "B5_P$65") (pintype "passive"))
      (node (ref "J5") (pin "P$65") (pinfunction "B5_P$65") (pintype "passive"))
      (node (ref "J6") (pin "P$65") (pinfunction "B5_P$65") (pintype "passive"))
    )
    (net (code "15") (name "H1-11") (class "Default")
      (node (ref "J1") (pin "P$96") (pinfunction "A6_P$96") (pintype "passive"))
      (node (ref "J2") (pin "P$96") (pinfunction "A6_P$96") (pintype "passive"))
      (node (ref "J3") (pin "P$96") (pinfunction "A6_P$96") (pintype "passive"))
      (node (ref "J4") (pin "P$96") (pinfunction "A6_P$96") (pintype "passive"))
      (node (ref "J5") (pin "P$96") (pinfunction "A6_P$96") (pintype "passive"))
      (node (ref "J6") (pin "P$96") (pinfunction "A6_P$96") (pintype "passive"))
    )
    (net (code "16") (name "H1-12") (class "Default")
      (node (ref "J1") (pin "P$66") (pinfunction "B6_P$66") (pintype "passive"))
      (node (ref "J2") (pin "P$66") (pinfunction "B6_P$66") (pintype "passive"))
      (node (ref "J3") (pin "P$66") (pinfunction "B6_P$66") (pintype "passive"))
      (node (ref "J4") (pin "P$66") (pinfunction "B6_P$66") (pintype "passive"))
      (node (ref "J5") (pin "P$66") (pinfunction "B6_P$66") (pintype "passive"))
      (node (ref "J6") (pin "P$66") (pinfunction "B6_P$66") (pintype "passive"))
    )
    (net (code "17") (name "H1-13") (class "Default")
      (node (ref "J1") (pin "P$97") (pinfunction "A7_P$97") (pintype "passive"))
      (node (ref "J2") (pin "P$97") (pinfunction "A7_P$97") (pintype "passive"))
      (node (ref "J3") (pin "P$97") (pinfunction "A7_P$97") (pintype "passive"))
      (node (ref "J4") (pin "P$97") (pinfunction "A7_P$97") (pintype "passive"))
      (node (ref "J5") (pin "P$97") (pinfunction "A7_P$97") (pintype "passive"))
      (node (ref "J6") (pin "P$97") (pinfunction "A7_P$97") (pintype "passive"))
    )
    (net (code "18") (name "H1-14") (class "Default")
      (node (ref "J1") (pin "P$67") (pinfunction "B7_P$67") (pintype "passive"))
      (node (ref "J2") (pin "P$67") (pinfunction "B7_P$67") (pintype "passive"))
      (node (ref "J3") (pin "P$67") (pinfunction "B7_P$67") (pintype "passive"))
      (node (ref "J4") (pin "P$67") (pinfunction "B7_P$67") (pintype "passive"))
      (node (ref "J5") (pin "P$67") (pinfunction "B7_P$67") (pintype "passive"))
      (node (ref "J6") (pin "P$67") (pinfunction "B7_P$67") (pintype "passive"))
    )
    (net (code "19") (name "H1-15") (class "Default")
      (node (ref "J1") (pin "P$98") (pinfunction "A8_P$98") (pintype "passive"))
      (node (ref "J2") (pin "P$98") (pinfunction "A8_P$98") (pintype "passive"))
      (node (ref "J3") (pin "P$98") (pinfunction "A8_P$98") (pintype "passive"))
      (node (ref "J4") (pin "P$98") (pinfunction "A8_P$98") (pintype "passive"))
      (node (ref "J5") (pin "P$98") (pinfunction "A8_P$98") (pintype "passive"))
      (node (ref "J6") (pin "P$98") (pinfunction "A8_P$98") (pintype "passive"))
    )
    (net (code "20") (name "H1-16") (class "Default")
      (node (ref "J1") (pin "P$68") (pinfunction "B8_P$68") (pintype "passive"))
      (node (ref "J2") (pin "P$68") (pinfunction "B8_P$68") (pintype "passive"))
      (node (ref "J3") (pin "P$68") (pinfunction "B8_P$68") (pintype "passive"))
      (node (ref "J4") (pin "P$68") (pinfunction "B8_P$68") (pintype "passive"))
      (node (ref "J5") (pin "P$68") (pinfunction "B8_P$68") (pintype "passive"))
      (node (ref "J6") (pin "P$68") (pinfunction "B8_P$68") (pintype "passive"))
    )
    (net (code "21") (name "H1-17") (class "Default")
      (node (ref "J1") (pin "P$99") (pinfunction "A9_P$99") (pintype "passive"))
      (node (ref "J2") (pin "P$99") (pinfunction "A9_P$99") (pintype "passive"))
      (node (ref "J3") (pin "P$99") (pinfunction "A9_P$99") (pintype "passive"))
      (node (ref "J4") (pin "P$99") (pinfunction "A9_P$99") (pintype "passive"))
      (node (ref "J5") (pin "P$99") (pinfunction "A9_P$99") (pintype "passive"))
      (node (ref "J6") (pin "P$99") (pinfunction "A9_P$99") (pintype "passive"))
    )
    (net (code "22") (name "H1-18") (class "Default")
      (node (ref "J1") (pin "P$69") (pinfunction "B9_P$69") (pintype "passive"))
      (node (ref "J2") (pin "P$69") (pinfunction "B9_P$69") (pintype "passive"))
      (node (ref "J3") (pin "P$69") (pinfunction "B9_P$69") (pintype "passive"))
      (node (ref "J4") (pin "P$69") (pinfunction "B9_P$69") (pintype "passive"))
      (node (ref "J5") (pin "P$69") (pinfunction "B9_P$69") (pintype "passive"))
      (node (ref "J6") (pin "P$69") (pinfunction "B9_P$69") (pintype "passive"))
    )
    (net (code "23") (name "H1-19") (class "Default")
      (node (ref "J1") (pin "P$100") (pinfunction "A10_P$100") (pintype "passive"))
      (node (ref "J2") (pin "P$100") (pinfunction "A10_P$100") (pintype "passive"))
      (node (ref "J3") (pin "P$100") (pinfunction "A10_P$100") (pintype "passive"))
      (node (ref "J4") (pin "P$100") (pinfunction "A10_P$100") (pintype "passive"))
      (node (ref "J5") (pin "P$100") (pinfunction "A10_P$100") (pintype "passive"))
      (node (ref "J6") (pin "P$100") (pinfunction "A10_P$100") (pintype "passive"))
    )
    (net (code "24") (name "H1-20") (class "Default")
      (node (ref "J1") (pin "P$70") (pinfunction "B10_P$70") (pintype "passive"))
      (node (ref "J2") (pin "P$70") (pinfunction "B10_P$70") (pintype "passive"))
      (node (ref "J3") (pin "P$70") (pinfunction "B10_P$70") (pintype "passive"))
      (node (ref "J4") (pin "P$70") (pinfunction "B10_P$70") (pintype "passive"))
      (node (ref "J5") (pin "P$70") (pinfunction "B10_P$70") (pintype "passive"))
      (node (ref "J6") (pin "P$70") (pinfunction "B10_P$70") (pintype "passive"))
    )
    (net (code "25") (name "H1-21") (class "Default")
      (node (ref "J1") (pin "P$101") (pinfunction "A11_P$101") (pintype "passive"))
      (node (ref "J2") (pin "P$101") (pinfunction "A11_P$101") (pintype "passive"))
      (node (ref "J3") (pin "P$101") (pinfunction "A11_P$101") (pintype "passive"))
      (node (ref "J4") (pin "P$101") (pinfunction "A11_P$101") (pintype "passive"))
      (node (ref "J5") (pin "P$101") (pinfunction "A11_P$101") (pintype "passive"))
      (node (ref "J6") (pin "P$101") (pinfunction "A11_P$101") (pintype "passive"))
    )
    (net (code "26") (name "H1-22") (class "Default")
      (node (ref "J1") (pin "P$71") (pinfunction "B11_P$71") (pintype "passive"))
      (node (ref "J2") (pin "P$71") (pinfunction "B11_P$71") (pintype "passive"))
      (node (ref "J3") (pin "P$71") (pinfunction "B11_P$71") (pintype "passive"))
      (node (ref "J4") (pin "P$71") (pinfunction "B11_P$71") (pintype "passive"))
      (node (ref "J5") (pin "P$71") (pinfunction "B11_P$71") (pintype "passive"))
      (node (ref "J6") (pin "P$71") (pinfunction "B11_P$71") (pintype "passive"))
    )
    (net (code "27") (name "H1-23") (class "Default")
      (node (ref "J1") (pin "P$102") (pinfunction "A12_P$102") (pintype "passive"))
      (node (ref "J2") (pin "P$102") (pinfunction "A12_P$102") (pintype "passive"))
      (node (ref "J3") (pin "P$102") (pinfunction "A12_P$102") (pintype "passive"))
      (node (ref "J4") (pin "P$102") (pinfunction "A12_P$102") (pintype "passive"))
      (node (ref "J5") (pin "P$102") (pinfunction "A12_P$102") (pintype "passive"))
      (node (ref "J6") (pin "P$102") (pinfunction "A12_P$102") (pintype "passive"))
    )
    (net (code "28") (name "H1-24") (class "Default")
      (node (ref "J1") (pin "P$72") (pinfunction "B12_P$72") (pintype "passive"))
      (node (ref "J2") (pin "P$72") (pinfunction "B12_P$72") (pintype "passive"))
      (node (ref "J3") (pin "P$72") (pinfunction "B12_P$72") (pintype "passive"))
      (node (ref "J4") (pin "P$72") (pinfunction "B12_P$72") (pintype "passive"))
      (node (ref "J5") (pin "P$72") (pinfunction "B12_P$72") (pintype "passive"))
      (node (ref "J6") (pin "P$72") (pinfunction "B12_P$72") (pintype "passive"))
    )
    (net (code "29") (name "H1-25") (class "Default")
      (node (ref "J1") (pin "P$103") (pinfunction "A13_P$103") (pintype "passive"))
      (node (ref "J2") (pin "P$103") (pinfunction "A13_P$103") (pintype "passive"))
      (node (ref "J3") (pin "P$103") (pinfunction "A13_P$103") (pintype "passive"))
      (node (ref "J4") (pin "P$103") (pinfunction "A13_P$103") (pintype "passive"))
      (node (ref "J5") (pin "P$103") (pinfunction "A13_P$103") (pintype "passive"))
      (node (ref "J6") (pin "P$103") (pinfunction "A13_P$103") (pintype "passive"))
    )
    (net (code "30") (name "H1-26") (class "Default")
      (node (ref "J1") (pin "P$73") (pinfunction "B13_P$73") (pintype "passive"))
      (node (ref "J2") (pin "P$73") (pinfunction "B13_P$73") (pintype "passive"))
      (node (ref "J3") (pin "P$73") (pinfunction "B13_P$73") (pintype "passive"))
      (node (ref "J4") (pin "P$73") (pinfunction "B13_P$73") (pintype "passive"))
      (node (ref "J5") (pin "P$73") (pinfunction "B13_P$73") (pintype "passive"))
      (node (ref "J6") (pin "P$73") (pinfunction "B13_P$73") (pintype "passive"))
    )
    (net (code "31") (name "H1-27") (class "Default")
      (node (ref "J1") (pin "P$104") (pinfunction "A14_P$104") (pintype "passive"))
      (node (ref "J2") (pin "P$104") (pinfunction "A14_P$104") (pintype "passive"))
      (node (ref "J3") (pin "P$104") (pinfunction "A14_P$104") (pintype "passive"))
      (node (ref "J4") (pin "P$104") (pinfunction "A14_P$104") (pintype "passive"))
      (node (ref "J5") (pin "P$104") (pinfunction "A14_P$104") (pintype "passive"))
      (node (ref "J6") (pin "P$104") (pinfunction "A14_P$104") (pintype "passive"))
    )
    (net (code "32") (name "H1-28") (class "Default")
      (node (ref "J1") (pin "P$74") (pinfunction "B14_P$74") (pintype "passive"))
      (node (ref "J2") (pin "P$74") (pinfunction "B14_P$74") (pintype "passive"))
      (node (ref "J3") (pin "P$74") (pinfunction "B14_P$74") (pintype "passive"))
      (node (ref "J4") (pin "P$74") (pinfunction "B14_P$74") (pintype "passive"))
      (node (ref "J5") (pin "P$74") (pinfunction "B14_P$74") (pintype "passive"))
      (node (ref "J6") (pin "P$74") (pinfunction "B14_P$74") (pintype "passive"))
    )
    (net (code "33") (name "H1-29") (class "Default")
      (node (ref "J1") (pin "P$105") (pinfunction "A15_P$105") (pintype "passive"))
      (node (ref "J2") (pin "P$105") (pinfunction "A15_P$105") (pintype "passive"))
      (node (ref "J3") (pin "P$105") (pinfunction "A15_P$105") (pintype "passive"))
      (node (ref "J4") (pin "P$105") (pinfunction "A15_P$105") (pintype "passive"))
      (node (ref "J5") (pin "P$105") (pinfunction "A15_P$105") (pintype "passive"))
      (node (ref "J6") (pin "P$105") (pinfunction "A15_P$105") (pintype "passive"))
    )
    (net (code "34") (name "H1-30") (class "Default")
      (node (ref "J1") (pin "P$75") (pinfunction "B15_P$75") (pintype "passive"))
      (node (ref "J2") (pin "P$75") (pinfunction "B15_P$75") (pintype "passive"))
      (node (ref "J3") (pin "P$75") (pinfunction "B15_P$75") (pintype "passive"))
      (node (ref "J4") (pin "P$75") (pinfunction "B15_P$75") (pintype "passive"))
      (node (ref "J5") (pin "P$75") (pinfunction "B15_P$75") (pintype "passive"))
      (node (ref "J6") (pin "P$75") (pinfunction "B15_P$75") (pintype "passive"))
    )
    (net (code "35") (name "H1-31") (class "Default")
      (node (ref "J1") (pin "P$106") (pinfunction "A16_P$106") (pintype "passive"))
      (node (ref "J2") (pin "P$106") (pinfunction "A16_P$106") (pintype "passive"))
      (node (ref "J3") (pin "P$106") (pinfunction "A16_P$106") (pintype "passive"))
      (node (ref "J4") (pin "P$106") (pinfunction "A16_P$106") (pintype "passive"))
      (node (ref "J5") (pin "P$106") (pinfunction "A16_P$106") (pintype "passive"))
      (node (ref "J6") (pin "P$106") (pinfunction "A16_P$106") (pintype "passive"))
    )
    (net (code "36") (name "H1-32") (class "Default")
      (node (ref "J1") (pin "P$76") (pinfunction "B16_P$76") (pintype "passive"))
      (node (ref "J2") (pin "P$76") (pinfunction "B16_P$76") (pintype "passive"))
      (node (ref "J3") (pin "P$76") (pinfunction "B16_P$76") (pintype "passive"))
      (node (ref "J4") (pin "P$76") (pinfunction "B16_P$76") (pintype "passive"))
      (node (ref "J5") (pin "P$76") (pinfunction "B16_P$76") (pintype "passive"))
      (node (ref "J6") (pin "P$76") (pinfunction "B16_P$76") (pintype "passive"))
    )
    (net (code "37") (name "H1-33") (class "Default")
      (node (ref "J1") (pin "P$107") (pinfunction "A17_P$107") (pintype "passive"))
      (node (ref "J2") (pin "P$107") (pinfunction "A17_P$107") (pintype "passive"))
      (node (ref "J3") (pin "P$107") (pinfunction "A17_P$107") (pintype "passive"))
      (node (ref "J4") (pin "P$107") (pinfunction "A17_P$107") (pintype "passive"))
      (node (ref "J5") (pin "P$107") (pinfunction "A17_P$107") (pintype "passive"))
      (node (ref "J6") (pin "P$107") (pinfunction "A17_P$107") (pintype "passive"))
    )
    (net (code "38") (name "H1-34") (class "Default")
      (node (ref "J1") (pin "P$77") (pinfunction "B17_P$77") (pintype "passive"))
      (node (ref "J2") (pin "P$77") (pinfunction "B17_P$77") (pintype "passive"))
      (node (ref "J3") (pin "P$77") (pinfunction "B17_P$77") (pintype "passive"))
      (node (ref "J4") (pin "P$77") (pinfunction "B17_P$77") (pintype "passive"))
      (node (ref "J5") (pin "P$77") (pinfunction "B17_P$77") (pintype "passive"))
      (node (ref "J6") (pin "P$77") (pinfunction "B17_P$77") (pintype "passive"))
    )
    (net (code "39") (name "H1-35") (class "Default")
      (node (ref "J1") (pin "P$108") (pinfunction "A18_P$108") (pintype "passive"))
      (node (ref "J2") (pin "P$108") (pinfunction "A18_P$108") (pintype "passive"))
      (node (ref "J3") (pin "P$108") (pinfunction "A18_P$108") (pintype "passive"))
      (node (ref "J4") (pin "P$108") (pinfunction "A18_P$108") (pintype "passive"))
      (node (ref "J5") (pin "P$108") (pinfunction "A18_P$108") (pintype "passive"))
      (node (ref "J6") (pin "P$108") (pinfunction "A18_P$108") (pintype "passive"))
    )
    (net (code "40") (name "H1-36") (class "Default")
      (node (ref "J1") (pin "P$78") (pinfunction "B18_P$78") (pintype "passive"))
      (node (ref "J2") (pin "P$78") (pinfunction "B18_P$78") (pintype "passive"))
      (node (ref "J3") (pin "P$78") (pinfunction "B18_P$78") (pintype "passive"))
      (node (ref "J4") (pin "P$78") (pinfunction "B18_P$78") (pintype "passive"))
      (node (ref "J5") (pin "P$78") (pinfunction "B18_P$78") (pintype "passive"))
      (node (ref "J6") (pin "P$78") (pinfunction "B18_P$78") (pintype "passive"))
    )
    (net (code "41") (name "H1-37") (class "Default")
      (node (ref "J1") (pin "P$109") (pinfunction "A19_P$109") (pintype "passive"))
      (node (ref "J2") (pin "P$109") (pinfunction "A19_P$109") (pintype "passive"))
      (node (ref "J3") (pin "P$109") (pinfunction "A19_P$109") (pintype "passive"))
      (node (ref "J4") (pin "P$109") (pinfunction "A19_P$109") (pintype "passive"))
      (node (ref "J5") (pin "P$109") (pinfunction "A19_P$109") (pintype "passive"))
      (node (ref "J6") (pin "P$109") (pinfunction "A19_P$109") (pintype "passive"))
    )
    (net (code "42") (name "H1-38") (class "Default")
      (node (ref "J1") (pin "P$79") (pinfunction "B19_P$79") (pintype "passive"))
      (node (ref "J2") (pin "P$79") (pinfunction "B19_P$79") (pintype "passive"))
      (node (ref "J3") (pin "P$79") (pinfunction "B19_P$79") (pintype "passive"))
      (node (ref "J4") (pin "P$79") (pinfunction "B19_P$79") (pintype "passive"))
      (node (ref "J5") (pin "P$79") (pinfunction "B19_P$79") (pintype "passive"))
      (node (ref "J6") (pin "P$79") (pinfunction "B19_P$79") (pintype "passive"))
    )
    (net (code "43") (name "H1-39") (class "Default")
      (node (ref "J1") (pin "P$110") (pinfunction "A20_P$110") (pintype "passive"))
      (node (ref "J2") (pin "P$110") (pinfunction "A20_P$110") (pintype "passive"))
      (node (ref "J3") (pin "P$110") (pinfunction "A20_P$110") (pintype "passive"))
      (node (ref "J4") (pin "P$110") (pinfunction "A20_P$110") (pintype "passive"))
      (node (ref "J5") (pin "P$110") (pinfunction "A20_P$110") (pintype "passive"))
      (node (ref "J6") (pin "P$110") (pinfunction "A20_P$110") (pintype "passive"))
    )
    (net (code "44") (name "H1-40") (class "Default")
      (node (ref "J1") (pin "P$80") (pinfunction "B20_P$80") (pintype "passive"))
      (node (ref "J2") (pin "P$80") (pinfunction "B20_P$80") (pintype "passive"))
      (node (ref "J3") (pin "P$80") (pinfunction "B20_P$80") (pintype "passive"))
      (node (ref "J4") (pin "P$80") (pinfunction "B20_P$80") (pintype "passive"))
      (node (ref "J5") (pin "P$80") (pinfunction "B20_P$80") (pintype "passive"))
      (node (ref "J6") (pin "P$80") (pinfunction "B20_P$80") (pintype "passive"))
    )
    (net (code "45") (name "H1-41") (class "Default")
      (node (ref "J1") (pin "P$111") (pinfunction "A21_P$111") (pintype "passive"))
      (node (ref "J2") (pin "P$111") (pinfunction "A21_P$111") (pintype "passive"))
      (node (ref "J3") (pin "P$111") (pinfunction "A21_P$111") (pintype "passive"))
      (node (ref "J4") (pin "P$111") (pinfunction "A21_P$111") (pintype "passive"))
      (node (ref "J5") (pin "P$111") (pinfunction "A21_P$111") (pintype "passive"))
      (node (ref "J6") (pin "P$111") (pinfunction "A21_P$111") (pintype "passive"))
    )
    (net (code "46") (name "H1-42") (class "Default")
      (node (ref "J1") (pin "P$81") (pinfunction "B21_P$81") (pintype "passive"))
      (node (ref "J2") (pin "P$81") (pinfunction "B21_P$81") (pintype "passive"))
      (node (ref "J3") (pin "P$81") (pinfunction "B21_P$81") (pintype "passive"))
      (node (ref "J4") (pin "P$81") (pinfunction "B21_P$81") (pintype "passive"))
      (node (ref "J5") (pin "P$81") (pinfunction "B21_P$81") (pintype "passive"))
      (node (ref "J6") (pin "P$81") (pinfunction "B21_P$81") (pintype "passive"))
    )
    (net (code "47") (name "H1-43") (class "Default")
      (node (ref "J1") (pin "P$112") (pinfunction "A22_P$112") (pintype "passive"))
      (node (ref "J2") (pin "P$112") (pinfunction "A22_P$112") (pintype "passive"))
      (node (ref "J3") (pin "P$112") (pinfunction "A22_P$112") (pintype "passive"))
      (node (ref "J4") (pin "P$112") (pinfunction "A22_P$112") (pintype "passive"))
      (node (ref "J5") (pin "P$112") (pinfunction "A22_P$112") (pintype "passive"))
      (node (ref "J6") (pin "P$112") (pinfunction "A22_P$112") (pintype "passive"))
    )
    (net (code "48") (name "H1-44") (class "Default")
      (node (ref "J1") (pin "P$82") (pinfunction "B22_P$82") (pintype "passive"))
      (node (ref "J2") (pin "P$82") (pinfunction "B22_P$82") (pintype "passive"))
      (node (ref "J3") (pin "P$82") (pinfunction "B22_P$82") (pintype "passive"))
      (node (ref "J4") (pin "P$82") (pinfunction "B22_P$82") (pintype "passive"))
      (node (ref "J5") (pin "P$82") (pinfunction "B22_P$82") (pintype "passive"))
      (node (ref "J6") (pin "P$82") (pinfunction "B22_P$82") (pintype "passive"))
    )
    (net (code "49") (name "H1-45") (class "Default")
      (node (ref "J1") (pin "P$113") (pinfunction "A23_P$113") (pintype "passive"))
      (node (ref "J2") (pin "P$113") (pinfunction "A23_P$113") (pintype "passive"))
      (node (ref "J3") (pin "P$113") (pinfunction "A23_P$113") (pintype "passive"))
      (node (ref "J4") (pin "P$113") (pinfunction "A23_P$113") (pintype "passive"))
      (node (ref "J5") (pin "P$113") (pinfunction "A23_P$113") (pintype "passive"))
      (node (ref "J6") (pin "P$113") (pinfunction "A23_P$113") (pintype "passive"))
    )
    (net (code "50") (name "H1-46") (class "Default")
      (node (ref "J1") (pin "P$83") (pinfunction "B23_P$83") (pintype "passive"))
      (node (ref "J2") (pin "P$83") (pinfunction "B23_P$83") (pintype "passive"))
      (node (ref "J3") (pin "P$83") (pinfunction "B23_P$83") (pintype "passive"))
      (node (ref "J4") (pin "P$83") (pinfunction "B23_P$83") (pintype "passive"))
      (node (ref "J5") (pin "P$83") (pinfunction "B23_P$83") (pintype "passive"))
      (node (ref "J6") (pin "P$83") (pinfunction "B23_P$83") (pintype "passive"))
    )
    (net (code "51") (name "H1-47") (class "Default")
      (node (ref "J1") (pin "P$114") (pinfunction "A24_P$114") (pintype "passive"))
      (node (ref "J2") (pin "P$114") (pinfunction "A24_P$114") (pintype "passive"))
      (node (ref "J3") (pin "P$114") (pinfunction "A24_P$114") (pintype "passive"))
      (node (ref "J4") (pin "P$114") (pinfunction "A24_P$114") (pintype "passive"))
      (node (ref "J5") (pin "P$114") (pinfunction "A24_P$114") (pintype "passive"))
      (node (ref "J6") (pin "P$114") (pinfunction "A24_P$114") (pintype "passive"))
    )
    (net (code "52") (name "H1-48") (class "Default")
      (node (ref "J1") (pin "P$84") (pinfunction "B24_P$84") (pintype "passive"))
      (node (ref "J2") (pin "P$84") (pinfunction "B24_P$84") (pintype "passive"))
      (node (ref "J3") (pin "P$84") (pinfunction "B24_P$84") (pintype "passive"))
      (node (ref "J4") (pin "P$84") (pinfunction "B24_P$84") (pintype "passive"))
      (node (ref "J5") (pin "P$84") (pinfunction "B24_P$84") (pintype "passive"))
      (node (ref "J6") (pin "P$84") (pinfunction "B24_P$84") (pintype "passive"))
    )
    (net (code "53") (name "H1-49") (class "Default")
      (node (ref "J1") (pin "P$115") (pinfunction "A25_P$115") (pintype "passive"))
      (node (ref "J2") (pin "P$115") (pinfunction "A25_P$115") (pintype "passive"))
      (node (ref "J3") (pin "P$115") (pinfunction "A25_P$115") (pintype "passive"))
      (node (ref "J4") (pin "P$115") (pinfunction "A25_P$115") (pintype "passive"))
      (node (ref "J5") (pin "P$115") (pinfunction "A25_P$115") (pintype "passive"))
      (node (ref "J6") (pin "P$115") (pinfunction "A25_P$115") (pintype "passive"))
    )
    (net (code "54") (name "H1-50") (class "Default")
      (node (ref "J1") (pin "P$85") (pinfunction "B25_P$85") (pintype "passive"))
      (node (ref "J2") (pin "P$85") (pinfunction "B25_P$85") (pintype "passive"))
      (node (ref "J3") (pin "P$85") (pinfunction "B25_P$85") (pintype "passive"))
      (node (ref "J4") (pin "P$85") (pinfunction "B25_P$85") (pintype "passive"))
      (node (ref "J5") (pin "P$85") (pinfunction "B25_P$85") (pintype "passive"))
      (node (ref "J6") (pin "P$85") (pinfunction "B25_P$85") (pintype "passive"))
    )
    (net (code "55") (name "H1-51") (class "Default")
      (node (ref "J1") (pin "P$116") (pinfunction "A26_P$116") (pintype "passive"))
      (node (ref "J2") (pin "P$116") (pinfunction "A26_P$116") (pintype "passive"))
      (node (ref "J3") (pin "P$116") (pinfunction "A26_P$116") (pintype "passive"))
      (node (ref "J4") (pin "P$116") (pinfunction "A26_P$116") (pintype "passive"))
      (node (ref "J5") (pin "P$116") (pinfunction "A26_P$116") (pintype "passive"))
      (node (ref "J6") (pin "P$116") (pinfunction "A26_P$116") (pintype "passive"))
    )
    (net (code "56") (name "H1-52") (class "Default")
      (node (ref "J1") (pin "P$86") (pinfunction "B26_P$86") (pintype "passive"))
      (node (ref "J2") (pin "P$86") (pinfunction "B26_P$86") (pintype "passive"))
      (node (ref "J3") (pin "P$86") (pinfunction "B26_P$86") (pintype "passive"))
      (node (ref "J4") (pin "P$86") (pinfunction "B26_P$86") (pintype "passive"))
      (node (ref "J5") (pin "P$86") (pinfunction "B26_P$86") (pintype "passive"))
      (node (ref "J6") (pin "P$86") (pinfunction "B26_P$86") (pintype "passive"))
    )
    (net (code "57") (name "H2-1") (class "Default")
      (node (ref "J1") (pin "P$31") (pinfunction "C1_P$31") (pintype "passive"))
      (node (ref "J2") (pin "P$31") (pinfunction "C1_P$31") (pintype "passive"))
      (node (ref "J3") (pin "P$31") (pinfunction "C1_P$31") (pintype "passive"))
      (node (ref "J4") (pin "P$31") (pinfunction "C1_P$31") (pintype "passive"))
      (node (ref "J5") (pin "P$31") (pinfunction "C1_P$31") (pintype "passive"))
      (node (ref "J6") (pin "P$31") (pinfunction "C1_P$31") (pintype "passive"))
    )
    (net (code "58") (name "H2-2") (class "Default")
      (node (ref "J1") (pin "P$1") (pinfunction "D1_P$1") (pintype "passive"))
      (node (ref "J2") (pin "P$1") (pinfunction "D1_P$1") (pintype "passive"))
      (node (ref "J3") (pin "P$1") (pinfunction "D1_P$1") (pintype "passive"))
      (node (ref "J4") (pin "P$1") (pinfunction "D1_P$1") (pintype "passive"))
      (node (ref "J5") (pin "P$1") (pinfunction "D1_P$1") (pintype "passive"))
      (node (ref "J6") (pin "P$1") (pinfunction "D1_P$1") (pintype "passive"))
    )
    (net (code "59") (name "H2-3") (class "Default")
      (node (ref "J1") (pin "P$32") (pinfunction "C2_P$32") (pintype "passive"))
      (node (ref "J2") (pin "P$32") (pinfunction "C2_P$32") (pintype "passive"))
      (node (ref "J3") (pin "P$32") (pinfunction "C2_P$32") (pintype "passive"))
      (node (ref "J4") (pin "P$32") (pinfunction "C2_P$32") (pintype "passive"))
      (node (ref "J5") (pin "P$32") (pinfunction "C2_P$32") (pintype "passive"))
      (node (ref "J6") (pin "P$32") (pinfunction "C2_P$32") (pintype "passive"))
    )
    (net (code "60") (name "H2-4") (class "Default")
      (node (ref "J1") (pin "P$2") (pinfunction "D2_P$2") (pintype "passive"))
      (node (ref "J2") (pin "P$2") (pinfunction "D2_P$2") (pintype "passive"))
      (node (ref "J3") (pin "P$2") (pinfunction "D2_P$2") (pintype "passive"))
      (node (ref "J4") (pin "P$2") (pinfunction "D2_P$2") (pintype "passive"))
      (node (ref "J5") (pin "P$2") (pinfunction "D2_P$2") (pintype "passive"))
      (node (ref "J6") (pin "P$2") (pinfunction "D2_P$2") (pintype "passive"))
    )
    (net (code "61") (name "H2-5") (class "Default")
      (node (ref "J1") (pin "P$33") (pinfunction "C3_P$33") (pintype "passive"))
      (node (ref "J2") (pin "P$33") (pinfunction "C3_P$33") (pintype "passive"))
      (node (ref "J3") (pin "P$33") (pinfunction "C3_P$33") (pintype "passive"))
      (node (ref "J4") (pin "P$33") (pinfunction "C3_P$33") (pintype "passive"))
      (node (ref "J5") (pin "P$33") (pinfunction "C3_P$33") (pintype "passive"))
      (node (ref "J6") (pin "P$33") (pinfunction "C3_P$33") (pintype "passive"))
    )
    (net (code "62") (name "H2-6") (class "Default")
      (node (ref "J1") (pin "P$3") (pinfunction "D3_P$3") (pintype "passive"))
      (node (ref "J2") (pin "P$3") (pinfunction "D3_P$3") (pintype "passive"))
      (node (ref "J3") (pin "P$3") (pinfunction "D3_P$3") (pintype "passive"))
      (node (ref "J4") (pin "P$3") (pinfunction "D3_P$3") (pintype "passive"))
      (node (ref "J5") (pin "P$3") (pinfunction "D3_P$3") (pintype "passive"))
      (node (ref "J6") (pin "P$3") (pinfunction "D3_P$3") (pintype "passive"))
    )
    (net (code "63") (name "H2-7") (class "Default")
      (node (ref "J1") (pin "P$34") (pinfunction "C4_P$34") (pintype "passive"))
      (node (ref "J2") (pin "P$34") (pinfunction "C4_P$34") (pintype "passive"))
      (node (ref "J3") (pin "P$34") (pinfunction "C4_P$34") (pintype "passive"))
      (node (ref "J4") (pin "P$34") (pinfunction "C4_P$34") (pintype "passive"))
      (node (ref "J5") (pin "P$34") (pinfunction "C4_P$34") (pintype "passive"))
      (node (ref "J6") (pin "P$34") (pinfunction "C4_P$34") (pintype "passive"))
    )
    (net (code "64") (name "H2-8") (class "Default")
      (node (ref "J1") (pin "P$4") (pinfunction "D4_P$4") (pintype "passive"))
      (node (ref "J2") (pin "P$4") (pinfunction "D4_P$4") (pintype "passive"))
      (node (ref "J3") (pin "P$4") (pinfunction "D4_P$4") (pintype "passive"))
      (node (ref "J4") (pin "P$4") (pinfunction "D4_P$4") (pintype "passive"))
      (node (ref "J5") (pin "P$4") (pinfunction "D4_P$4") (pintype "passive"))
      (node (ref "J6") (pin "P$4") (pinfunction "D4_P$4") (pintype "passive"))
    )
    (net (code "65") (name "H2-10") (class "Default")
      (node (ref "J1") (pin "P$5") (pinfunction "D5_P$5") (pintype "passive"))
      (node (ref "J2") (pin "P$5") (pinfunction "D5_P$5") (pintype "passive"))
      (node (ref "J3") (pin "P$5") (pinfunction "D5_P$5") (pintype "passive"))
      (node (ref "J4") (pin "P$5") (pinfunction "D5_P$5") (pintype "passive"))
      (node (ref "J5") (pin "P$5") (pinfunction "D5_P$5") (pintype "passive"))
      (node (ref "J6") (pin "P$5") (pinfunction "D5_P$5") (pintype "passive"))
    )
    (net (code "66") (name "H2-11") (class "Default")
      (node (ref "J1") (pin "P$36") (pinfunction "C6_P$36") (pintype "passive"))
      (node (ref "J2") (pin "P$36") (pinfunction "C6_P$36") (pintype "passive"))
      (node (ref "J3") (pin "P$36") (pinfunction "C6_P$36") (pintype "passive"))
      (node (ref "J4") (pin "P$36") (pinfunction "C6_P$36") (pintype "passive"))
      (node (ref "J5") (pin "P$36") (pinfunction "C6_P$36") (pintype "passive"))
      (node (ref "J6") (pin "P$36") (pinfunction "C6_P$36") (pintype "passive"))
    )
    (net (code "67") (name "H2-12") (class "Default")
      (node (ref "J1") (pin "P$6") (pinfunction "D6_P$6") (pintype "passive"))
      (node (ref "J2") (pin "P$6") (pinfunction "D6_P$6") (pintype "passive"))
      (node (ref "J3") (pin "P$6") (pinfunction "D6_P$6") (pintype "passive"))
      (node (ref "J4") (pin "P$6") (pinfunction "D6_P$6") (pintype "passive"))
      (node (ref "J5") (pin "P$6") (pinfunction "D6_P$6") (pintype "passive"))
      (node (ref "J6") (pin "P$6") (pinfunction "D6_P$6") (pintype "passive"))
    )
    (net (code "68") (name "H2-13") (class "Default")
      (node (ref "J1") (pin "P$37") (pinfunction "C7_P$37") (pintype "passive"))
      (node (ref "J2") (pin "P$37") (pinfunction "C7_P$37") (pintype "passive"))
      (node (ref "J3") (pin "P$37") (pinfunction "C7_P$37") (pintype "passive"))
      (node (ref "J4") (pin "P$37") (pinfunction "C7_P$37") (pintype "passive"))
      (node (ref "J5") (pin "P$37") (pinfunction "C7_P$37") (pintype "passive"))
      (node (ref "J6") (pin "P$37") (pinfunction "C7_P$37") (pintype "passive"))
    )
    (net (code "69") (name "H2-15") (class "Default")
      (node (ref "J1") (pin "P$38") (pinfunction "C8_P$38") (pintype "passive"))
      (node (ref "J2") (pin "P$38") (pinfunction "C8_P$38") (pintype "passive"))
      (node (ref "J3") (pin "P$38") (pinfunction "C8_P$38") (pintype "passive"))
      (node (ref "J4") (pin "P$38") (pinfunction "C8_P$38") (pintype "passive"))
      (node (ref "J5") (pin "P$38") (pinfunction "C8_P$38") (pintype "passive"))
      (node (ref "J6") (pin "P$38") (pinfunction "C8_P$38") (pintype "passive"))
    )
    (net (code "70") (name "H2-16") (class "Default")
      (node (ref "J1") (pin "P$8") (pinfunction "D8_P$8") (pintype "passive"))
      (node (ref "J2") (pin "P$8") (pinfunction "D8_P$8") (pintype "passive"))
      (node (ref "J3") (pin "P$8") (pinfunction "D8_P$8") (pintype "passive"))
      (node (ref "J4") (pin "P$8") (pinfunction "D8_P$8") (pintype "passive"))
      (node (ref "J5") (pin "P$8") (pinfunction "D8_P$8") (pintype "passive"))
      (node (ref "J6") (pin "P$8") (pinfunction "D8_P$8") (pintype "passive"))
    )
    (net (code "71") (name "H2-18") (class "Default")
      (node (ref "J1") (pin "P$9") (pinfunction "D9_P$9") (pintype "passive"))
      (node (ref "J2") (pin "P$9") (pinfunction "D9_P$9") (pintype "passive"))
      (node (ref "J3") (pin "P$9") (pinfunction "D9_P$9") (pintype "passive"))
      (node (ref "J4") (pin "P$9") (pinfunction "D9_P$9") (pintype "passive"))
      (node (ref "J5") (pin "P$9") (pinfunction "D9_P$9") (pintype "passive"))
      (node (ref "J6") (pin "P$9") (pinfunction "D9_P$9") (pintype "passive"))
    )
    (net (code "72") (name "H2-19") (class "Default")
      (node (ref "J1") (pin "P$40") (pinfunction "C10_P$40") (pintype "passive"))
      (node (ref "J2") (pin "P$40") (pinfunction "C10_P$40") (pintype "passive"))
      (node (ref "J3") (pin "P$40") (pinfunction "C10_P$40") (pintype "passive"))
      (node (ref "J4") (pin "P$40") (pinfunction "C10_P$40") (pintype "passive"))
      (node (ref "J5") (pin "P$40") (pinfunction "C10_P$40") (pintype "passive"))
      (node (ref "J6") (pin "P$40") (pinfunction "C10_P$40") (pintype "passive"))
    )
    (net (code "73") (name "H2-20") (class "Default")
      (node (ref "J1") (pin "P$10") (pinfunction "D10_P$10") (pintype "passive"))
      (node (ref "J2") (pin "P$10") (pinfunction "D10_P$10") (pintype "passive"))
      (node (ref "J3") (pin "P$10") (pinfunction "D10_P$10") (pintype "passive"))
      (node (ref "J4") (pin "P$10") (pinfunction "D10_P$10") (pintype "passive"))
      (node (ref "J5") (pin "P$10") (pinfunction "D10_P$10") (pintype "passive"))
      (node (ref "J6") (pin "P$10") (pinfunction "D10_P$10") (pintype "passive"))
    )
    (net (code "74") (name "H2-31") (class "Default")
      (node (ref "J1") (pin "P$46") (pinfunction "C16_P$46") (pintype "passive"))
      (node (ref "J2") (pin "P$46") (pinfunction "C16_P$46") (pintype "passive"))
      (node (ref "J3") (pin "P$46") (pinfunction "C16_P$46") (pintype "passive"))
      (node (ref "J4") (pin "P$46") (pinfunction "C16_P$46") (pintype "passive"))
      (node (ref "J5") (pin "P$46") (pinfunction "C16_P$46") (pintype "passive"))
      (node (ref "J6") (pin "P$46") (pinfunction "C16_P$46") (pintype "passive"))
    )
    (net (code "75") (name "H2-33") (class "Default")
      (node (ref "J1") (pin "P$47") (pinfunction "C17_P$47") (pintype "passive"))
      (node (ref "J2") (pin "P$47") (pinfunction "C17_P$47") (pintype "passive"))
      (node (ref "J3") (pin "P$47") (pinfunction "C17_P$47") (pintype "passive"))
      (node (ref "J4") (pin "P$47") (pinfunction "C17_P$47") (pintype "passive"))
      (node (ref "J5") (pin "P$47") (pinfunction "C17_P$47") (pintype "passive"))
      (node (ref "J6") (pin "P$47") (pinfunction "C17_P$47") (pintype "passive"))
    )
    (net (code "76") (name "H2-34") (class "Default")
      (node (ref "J1") (pin "P$17") (pinfunction "D17_P$17") (pintype "passive"))
      (node (ref "J2") (pin "P$17") (pinfunction "D17_P$17") (pintype "passive"))
      (node (ref "J3") (pin "P$17") (pinfunction "D17_P$17") (pintype "passive"))
      (node (ref "J4") (pin "P$17") (pinfunction "D17_P$17") (pintype "passive"))
      (node (ref "J5") (pin "P$17") (pinfunction "D17_P$17") (pintype "passive"))
      (node (ref "J6") (pin "P$17") (pinfunction "D17_P$17") (pintype "passive"))
    )
    (net (code "77") (name "H2-35") (class "Default")
      (node (ref "J1") (pin "P$48") (pinfunction "C18_P$48") (pintype "passive"))
      (node (ref "J2") (pin "P$48") (pinfunction "C18_P$48") (pintype "passive"))
      (node (ref "J3") (pin "P$48") (pinfunction "C18_P$48") (pintype "passive"))
      (node (ref "J4") (pin "P$48") (pinfunction "C18_P$48") (pintype "passive"))
      (node (ref "J5") (pin "P$48") (pinfunction "C18_P$48") (pintype "passive"))
      (node (ref "J6") (pin "P$48") (pinfunction "C18_P$48") (pintype "passive"))
    )
    (net (code "78") (name "H2-36") (class "Default")
      (node (ref "J1") (pin "P$18") (pinfunction "D18_P$18") (pintype "passive"))
      (node (ref "J2") (pin "P$18") (pinfunction "D18_P$18") (pintype "passive"))
      (node (ref "J3") (pin "P$18") (pinfunction "D18_P$18") (pintype "passive"))
      (node (ref "J4") (pin "P$18") (pinfunction "D18_P$18") (pintype "passive"))
      (node (ref "J5") (pin "P$18") (pinfunction "D18_P$18") (pintype "passive"))
      (node (ref "J6") (pin "P$18") (pinfunction "D18_P$18") (pintype "passive"))
    )
    (net (code "79") (name "H2-37") (class "Default")
      (node (ref "J1") (pin "P$49") (pinfunction "C19_P$49") (pintype "passive"))
      (node (ref "J2") (pin "P$49") (pinfunction "C19_P$49") (pintype "passive"))
      (node (ref "J3") (pin "P$49") (pinfunction "C19_P$49") (pintype "passive"))
      (node (ref "J4") (pin "P$49") (pinfunction "C19_P$49") (pintype "passive"))
      (node (ref "J5") (pin "P$49") (pinfunction "C19_P$49") (pintype "passive"))
      (node (ref "J6") (pin "P$49") (pinfunction "C19_P$49") (pintype "passive"))
    )
    (net (code "80") (name "H2-38") (class "Default")
      (node (ref "J1") (pin "P$19") (pinfunction "D19_P$19") (pintype "passive"))
      (node (ref "J2") (pin "P$19") (pinfunction "D19_P$19") (pintype "passive"))
      (node (ref "J3") (pin "P$19") (pinfunction "D19_P$19") (pintype "passive"))
      (node (ref "J4") (pin "P$19") (pinfunction "D19_P$19") (pintype "passive"))
      (node (ref "J5") (pin "P$19") (pinfunction "D19_P$19") (pintype "passive"))
      (node (ref "J6") (pin "P$19") (pinfunction "D19_P$19") (pintype "passive"))
    )
    (net (code "81") (name "H2-39") (class "Default")
      (node (ref "J1") (pin "P$50") (pinfunction "C20_P$50") (pintype "passive"))
      (node (ref "J2") (pin "P$50") (pinfunction "C20_P$50") (pintype "passive"))
      (node (ref "J3") (pin "P$50") (pinfunction "C20_P$50") (pintype "passive"))
      (node (ref "J4") (pin "P$50") (pinfunction "C20_P$50") (pintype "passive"))
      (node (ref "J5") (pin "P$50") (pinfunction "C20_P$50") (pintype "passive"))
      (node (ref "J6") (pin "P$50") (pinfunction "C20_P$50") (pintype "passive"))
    )
    (net (code "82") (name "H2-40") (class "Default")
      (node (ref "J1") (pin "P$20") (pinfunction "D20_P$20") (pintype "passive"))
      (node (ref "J2") (pin "P$20") (pinfunction "D20_P$20") (pintype "passive"))
      (node (ref "J3") (pin "P$20") (pinfunction "D20_P$20") (pintype "passive"))
      (node (ref "J4") (pin "P$20") (pinfunction "D20_P$20") (pintype "passive"))
      (node (ref "J5") (pin "P$20") (pinfunction "D20_P$20") (pintype "passive"))
      (node (ref "J6") (pin "P$20") (pinfunction "D20_P$20") (pintype "passive"))
    )
    (net (code "83") (name "H2-41") (class "Default")
      (node (ref "J1") (pin "P$51") (pinfunction "C21_P$51") (pintype "passive"))
      (node (ref "J2") (pin "P$51") (pinfunction "C21_P$51") (pintype "passive"))
      (node (ref "J3") (pin "P$51") (pinfunction "C21_P$51") (pintype "passive"))
      (node (ref "J4") (pin "P$51") (pinfunction "C21_P$51") (pintype "passive"))
      (node (ref "J5") (pin "P$51") (pinfunction "C21_P$51") (pintype "passive"))
      (node (ref "J6") (pin "P$51") (pinfunction "C21_P$51") (pintype "passive"))
    )
    (net (code "84") (name "H2-42") (class "Default")
      (node (ref "J1") (pin "P$21") (pinfunction "D21_P$21") (pintype "passive"))
      (node (ref "J2") (pin "P$21") (pinfunction "D21_P$21") (pintype "passive"))
      (node (ref "J3") (pin "P$21") (pinfunction "D21_P$21") (pintype "passive"))
      (node (ref "J4") (pin "P$21") (pinfunction "D21_P$21") (pintype "passive"))
      (node (ref "J5") (pin "P$21") (pinfunction "D21_P$21") (pintype "passive"))
      (node (ref "J6") (pin "P$21") (pinfunction "D21_P$21") (pintype "passive"))
    )
    (net (code "85") (name "H2-43") (class "Default")
      (node (ref "J1") (pin "P$52") (pinfunction "C22_P$52") (pintype "passive"))
      (node (ref "J2") (pin "P$52") (pinfunction "C22_P$52") (pintype "passive"))
      (node (ref "J3") (pin "P$52") (pinfunction "C22_P$52") (pintype "passive"))
      (node (ref "J4") (pin "P$52") (pinfunction "C22_P$52") (pintype "passive"))
      (node (ref "J5") (pin "P$52") (pinfunction "C22_P$52") (pintype "passive"))
      (node (ref "J6") (pin "P$52") (pinfunction "C22_P$52") (pintype "passive"))
    )
    (net (code "86") (name "H2-44") (class "Default")
      (node (ref "J1") (pin "P$22") (pinfunction "D22_P$22") (pintype "passive"))
      (node (ref "J2") (pin "P$22") (pinfunction "D22_P$22") (pintype "passive"))
      (node (ref "J3") (pin "P$22") (pinfunction "D22_P$22") (pintype "passive"))
      (node (ref "J4") (pin "P$22") (pinfunction "D22_P$22") (pintype "passive"))
      (node (ref "J5") (pin "P$22") (pinfunction "D22_P$22") (pintype "passive"))
      (node (ref "J6") (pin "P$22") (pinfunction "D22_P$22") (pintype "passive"))
    )
    (net (code "87") (name "H2-49") (class "Default")
      (node (ref "J1") (pin "P$55") (pinfunction "C25_P$55") (pintype "passive"))
      (node (ref "J2") (pin "P$55") (pinfunction "C25_P$55") (pintype "passive"))
      (node (ref "J3") (pin "P$55") (pinfunction "C25_P$55") (pintype "passive"))
      (node (ref "J4") (pin "P$55") (pinfunction "C25_P$55") (pintype "passive"))
      (node (ref "J5") (pin "P$55") (pinfunction "C25_P$55") (pintype "passive"))
      (node (ref "J6") (pin "P$55") (pinfunction "C25_P$55") (pintype "passive"))
    )
    (net (code "88") (name "H2-50") (class "Default")
      (node (ref "J1") (pin "P$25") (pinfunction "D25_P$25") (pintype "passive"))
      (node (ref "J2") (pin "P$25") (pinfunction "D25_P$25") (pintype "passive"))
      (node (ref "J3") (pin "P$25") (pinfunction "D25_P$25") (pintype "passive"))
      (node (ref "J4") (pin "P$25") (pinfunction "D25_P$25") (pintype "passive"))
      (node (ref "J5") (pin "P$25") (pinfunction "D25_P$25") (pintype "passive"))
      (node (ref "J6") (pin "P$25") (pinfunction "D25_P$25") (pintype "passive"))
    )
    (net (code "89") (name "H2-51") (class "Default")
      (node (ref "J1") (pin "P$56") (pinfunction "C26_P$56") (pintype "passive"))
      (node (ref "J2") (pin "P$56") (pinfunction "C26_P$56") (pintype "passive"))
      (node (ref "J3") (pin "P$56") (pinfunction "C26_P$56") (pintype "passive"))
      (node (ref "J4") (pin "P$56") (pinfunction "C26_P$56") (pintype "passive"))
      (node (ref "J5") (pin "P$56") (pinfunction "C26_P$56") (pintype "passive"))
      (node (ref "J6") (pin "P$56") (pinfunction "C26_P$56") (pintype "passive"))
    )
    (net (code "90") (name "H2-52") (class "Default")
      (node (ref "J1") (pin "P$26") (pinfunction "D26_P$26") (pintype "passive"))
      (node (ref "J2") (pin "P$26") (pinfunction "D26_P$26") (pintype "passive"))
      (node (ref "J3") (pin "P$26") (pinfunction "D26_P$26") (pintype "passive"))
      (node (ref "J4") (pin "P$26") (pinfunction "D26_P$26") (pintype "passive"))
      (node (ref "J5") (pin "P$26") (pinfunction "D26_P$26") (pintype "passive"))
      (node (ref "J6") (pin "P$26") (pinfunction "D26_P$26") (pintype "passive"))
    )
    (net (code "91") (name "UN01") (class "Default")
      (node (ref "J1") (pin "P$117") (pinfunction "A27_P$117") (pintype "passive"))
      (node (ref "J2") (pin "P$117") (pinfunction "A27_P$117") (pintype "passive"))
      (node (ref "J3") (pin "P$117") (pinfunction "A27_P$117") (pintype "passive"))
      (node (ref "J4") (pin "P$117") (pinfunction "A27_P$117") (pintype "passive"))
      (node (ref "J5") (pin "P$117") (pinfunction "A27_P$117") (pintype "passive"))
      (node (ref "J6") (pin "P$117") (pinfunction "A27_P$117") (pintype "passive"))
    )
    (net (code "92") (name "UN02") (class "Default")
      (node (ref "J1") (pin "P$87") (pinfunction "B27_P$87") (pintype "passive"))
      (node (ref "J2") (pin "P$87") (pinfunction "B27_P$87") (pintype "passive"))
      (node (ref "J3") (pin "P$87") (pinfunction "B27_P$87") (pintype "passive"))
      (node (ref "J4") (pin "P$87") (pinfunction "B27_P$87") (pintype "passive"))
      (node (ref "J5") (pin "P$87") (pinfunction "B27_P$87") (pintype "passive"))
      (node (ref "J6") (pin "P$87") (pinfunction "B27_P$87") (pintype "passive"))
    )
    (net (code "93") (name "UN03") (class "Default")
      (node (ref "J1") (pin "P$118") (pinfunction "A28_P$118") (pintype "passive"))
      (node (ref "J2") (pin "P$118") (pinfunction "A28_P$118") (pintype "passive"))
      (node (ref "J3") (pin "P$118") (pinfunction "A28_P$118") (pintype "passive"))
      (node (ref "J4") (pin "P$118") (pinfunction "A28_P$118") (pintype "passive"))
      (node (ref "J5") (pin "P$118") (pinfunction "A28_P$118") (pintype "passive"))
      (node (ref "J6") (pin "P$118") (pinfunction "A28_P$118") (pintype "passive"))
    )
    (net (code "94") (name "UN04") (class "Default")
      (node (ref "J1") (pin "P$88") (pinfunction "B28_P$88") (pintype "passive"))
      (node (ref "J2") (pin "P$88") (pinfunction "B28_P$88") (pintype "passive"))
      (node (ref "J3") (pin "P$88") (pinfunction "B28_P$88") (pintype "passive"))
      (node (ref "J4") (pin "P$88") (pinfunction "B28_P$88") (pintype "passive"))
      (node (ref "J5") (pin "P$88") (pinfunction "B28_P$88") (pintype "passive"))
      (node (ref "J6") (pin "P$88") (pinfunction "B28_P$88") (pintype "passive"))
    )
    (net (code "95") (name "UN05") (class "Default")
      (node (ref "J1") (pin "P$119") (pinfunction "A29_P$119") (pintype "passive"))
      (node (ref "J2") (pin "P$119") (pinfunction "A29_P$119") (pintype "passive"))
      (node (ref "J3") (pin "P$119") (pinfunction "A29_P$119") (pintype "passive"))
      (node (ref "J4") (pin "P$119") (pinfunction "A29_P$119") (pintype "passive"))
      (node (ref "J5") (pin "P$119") (pinfunction "A29_P$119") (pintype "passive"))
      (node (ref "J6") (pin "P$119") (pinfunction "A29_P$119") (pintype "passive"))
    )
    (net (code "96") (name "UN06") (class "Default")
      (node (ref "J1") (pin "P$89") (pinfunction "B29_P$89") (pintype "passive"))
      (node (ref "J2") (pin "P$89") (pinfunction "B29_P$89") (pintype "passive"))
      (node (ref "J3") (pin "P$89") (pinfunction "B29_P$89") (pintype "passive"))
      (node (ref "J4") (pin "P$89") (pinfunction "B29_P$89") (pintype "passive"))
      (node (ref "J5") (pin "P$89") (pinfunction "B29_P$89") (pintype "passive"))
      (node (ref "J6") (pin "P$89") (pinfunction "B29_P$89") (pintype "passive"))
    )
    (net (code "97") (name "UN07") (class "Default")
      (node (ref "J1") (pin "P$120") (pinfunction "A30_P$120") (pintype "passive"))
      (node (ref "J2") (pin "P$120") (pinfunction "A30_P$120") (pintype "passive"))
      (node (ref "J3") (pin "P$120") (pinfunction "A30_P$120") (pintype "passive"))
      (node (ref "J4") (pin "P$120") (pinfunction "A30_P$120") (pintype "passive"))
      (node (ref "J5") (pin "P$120") (pinfunction "A30_P$120") (pintype "passive"))
      (node (ref "J6") (pin "P$120") (pinfunction "A30_P$120") (pintype "passive"))
    )
    (net (code "98") (name "UN08") (class "Default")
      (node (ref "J1") (pin "P$90") (pinfunction "B30_P$90") (pintype "passive"))
      (node (ref "J2") (pin "P$90") (pinfunction "B30_P$90") (pintype "passive"))
      (node (ref "J3") (pin "P$90") (pinfunction "B30_P$90") (pintype "passive"))
      (node (ref "J4") (pin "P$90") (pinfunction "B30_P$90") (pintype "passive"))
      (node (ref "J5") (pin "P$90") (pinfunction "B30_P$90") (pintype "passive"))
      (node (ref "J6") (pin "P$90") (pinfunction "B30_P$90") (pintype "passive"))
    )
    (net (code "99") (name "UN09") (class "Default")
      (node (ref "J1") (pin "P$57") (pinfunction "C27_P$57") (pintype "passive"))
      (node (ref "J2") (pin "P$57") (pinfunction "C27_P$57") (pintype "passive"))
      (node (ref "J3") (pin "P$57") (pinfunction "C27_P$57") (pintype "passive"))
      (node (ref "J4") (pin "P$57") (pinfunction "C27_P$57") (pintype "passive"))
      (node (ref "J5") (pin "P$57") (pinfunction "C27_P$57") (pintype "passive"))
      (node (ref "J6") (pin "P$57") (pinfunction "C27_P$57") (pintype "passive"))
    )
    (net (code "100") (name "UN10") (class "Default")
      (node (ref "J1") (pin "P$27") (pinfunction "D27_P$27") (pintype "passive"))
      (node (ref "J2") (pin "P$27") (pinfunction "D27_P$27") (pintype "passive"))
      (node (ref "J3") (pin "P$27") (pinfunction "D27_P$27") (pintype "passive"))
      (node (ref "J4") (pin "P$27") (pinfunction "D27_P$27") (pintype "passive"))
      (node (ref "J5") (pin "P$27") (pinfunction "D27_P$27") (pintype "passive"))
      (node (ref "J6") (pin "P$27") (pinfunction "D27_P$27") (pintype "passive"))
    )
    (net (code "101") (name "UN11") (class "Default")
      (node (ref "J1") (pin "P$58") (pinfunction "C28_P$58") (pintype "passive"))
      (node (ref "J2") (pin "P$58") (pinfunction "C28_P$58") (pintype "passive"))
      (node (ref "J3") (pin "P$58") (pinfunction "C28_P$58") (pintype "passive"))
      (node (ref "J4") (pin "P$58") (pinfunction "C28_P$58") (pintype "passive"))
      (node (ref "J5") (pin "P$58") (pinfunction "C28_P$58") (pintype "passive"))
      (node (ref "J6") (pin "P$58") (pinfunction "C28_P$58") (pintype "passive"))
    )
    (net (code "102") (name "UN12") (class "Default")
      (node (ref "J1") (pin "P$28") (pinfunction "D28_P$28") (pintype "passive"))
      (node (ref "J2") (pin "P$28") (pinfunction "D28_P$28") (pintype "passive"))
      (node (ref "J3") (pin "P$28") (pinfunction "D28_P$28") (pintype "passive"))
      (node (ref "J4") (pin "P$28") (pinfunction "D28_P$28") (pintype "passive"))
      (node (ref "J5") (pin "P$28") (pinfunction "D28_P$28") (pintype "passive"))
      (node (ref "J6") (pin "P$28") (pinfunction "D28_P$28") (pintype "passive"))
    )
    (net (code "103") (name "UN13") (class "Default")
      (node (ref "J1") (pin "P$59") (pinfunction "C29_P$59") (pintype "passive"))
      (node (ref "J2") (pin "P$59") (pinfunction "C29_P$59") (pintype "passive"))
      (node (ref "J3") (pin "P$59") (pinfunction "C29_P$59") (pintype "passive"))
      (node (ref "J4") (pin "P$59") (pinfunction "C29_P$59") (pintype "passive"))
      (node (ref "J5") (pin "P$59") (pinfunction "C29_P$59") (pintype "passive"))
      (node (ref "J6") (pin "P$59") (pinfunction "C29_P$59") (pintype "passive"))
    )
    (net (code "104") (name "UN14") (class "Default")
      (node (ref "J1") (pin "P$29") (pinfunction "D29_P$29") (pintype "passive"))
      (node (ref "J2") (pin "P$29") (pinfunction "D29_P$29") (pintype "passive"))
      (node (ref "J3") (pin "P$29") (pinfunction "D29_P$29") (pintype "passive"))
      (node (ref "J4") (pin "P$29") (pinfunction "D29_P$29") (pintype "passive"))
      (node (ref "J5") (pin "P$29") (pinfunction "D29_P$29") (pintype "passive"))
      (node (ref "J6") (pin "P$29") (pinfunction "D29_P$29") (pintype "passive"))
    )
    (net (code "105") (name "UN15") (class "Default")
      (node (ref "J1") (pin "P$60") (pinfunction "C30_P$60") (pintype "passive"))
      (node (ref "J2") (pin "P$60") (pinfunction "C30_P$60") (pintype "passive"))
      (node (ref "J3") (pin "P$60") (pinfunction "C30_P$60") (pintype "passive"))
      (node (ref "J4") (pin "P$60") (pinfunction "C30_P$60") (pintype "passive"))
      (node (ref "J5") (pin "P$60") (pinfunction "C30_P$60") (pintype "passive"))
      (node (ref "J6") (pin "P$60") (pinfunction "C30_P$60") (pintype "passive"))
    )
    (net (code "106") (name "UN16") (class "Default")
      (node (ref "J1") (pin "P$30") (pinfunction "D30_P$30") (pintype "passive"))
      (node (ref "J2") (pin "P$30") (pinfunction "D30_P$30") (pintype "passive"))
      (node (ref "J3") (pin "P$30") (pinfunction "D30_P$30") (pintype "passive"))
      (node (ref "J4") (pin "P$30") (pinfunction "D30_P$30") (pintype "passive"))
      (node (ref "J5") (pin "P$30") (pinfunction "D30_P$30") (pintype "passive"))
      (node (ref "J6") (pin "P$30") (pinfunction "D30_P$30") (pintype "passive"))
    )
    (net (code "107") (name "VBAT") (class "Default")
      (node (ref "J1") (pin "P$23") (pinfunction "D23_P$23") (pintype "passive"))
      (node (ref "J1") (pin "P$53") (pinfunction "C23_P$53") (pintype "passive"))
      (node (ref "J2") (pin "P$23") (pinfunction "D23_P$23") (pintype "passive"))
      (node (ref "J2") (pin "P$53") (pinfunction "C23_P$53") (pintype "passive"))
      (node (ref "J3") (pin "P$23") (pinfunction "D23_P$23") (pintype "passive"))
      (node (ref "J3") (pin "P$53") (pinfunction "C23_P$53") (pintype "passive"))
      (node (ref "J4") (pin "P$23") (pinfunction "D23_P$23") (pintype "passive"))
      (node (ref "J4") (pin "P$53") (pinfunction "C23_P$53") (pintype "passive"))
      (node (ref "U$6") (pin "P$1") (pinfunction "PIN_P$1") (pintype "bidirectional"))
    )
    (net (code "108") (name "unconnected-(J5-C12-PadP$42)") (class "Default")
      (node (ref "J5") (pin "P$42") (pinfunction "C12_P$42") (pintype "passive"))
    )
    (net (code "109") (name "unconnected-(J5-C13-PadP$43)") (class "Default")
      (node (ref "J5") (pin "P$43") (pinfunction "C13_P$43") (pintype "passive"))
    )
    (net (code "110") (name "unconnected-(J5-C14-PadP$44)") (class "Default")
      (node (ref "J5") (pin "P$44") (pinfunction "C14_P$44") (pintype "passive"))
    )
    (net (code "111") (name "unconnected-(J5-C23-PadP$53)") (class "Default")
      (node (ref "J5") (pin "P$53") (pinfunction "C23_P$53") (pintype "passive"))
    )
    (net (code "112") (name "unconnected-(J5-D12-PadP$12)") (class "Default")
      (node (ref "J5") (pin "P$12") (pinfunction "D12_P$12") (pintype "passive"))
    )
    (net (code "113") (name "unconnected-(J5-D13-PadP$13)") (class "Default")
      (node (ref "J5") (pin "P$13") (pinfunction "D13_P$13") (pintype "passive"))
    )
    (net (code "114") (name "unconnected-(J5-D14-PadP$14)") (class "Default")
      (node (ref "J5") (pin "P$14") (pinfunction "D14_P$14") (pintype "passive"))
    )
    (net (code "115") (name "unconnected-(J5-D23-PadP$23)") (class "Default")
      (node (ref "J5") (pin "P$23") (pinfunction "D23_P$23") (pintype "passive"))
    )
    (net (code "116") (name "unconnected-(J6-C12-PadP$42)") (class "Default")
      (node (ref "J6") (pin "P$42") (pinfunction "C12_P$42") (pintype "passive"))
    )
    (net (code "117") (name "unconnected-(J6-C13-PadP$43)") (class "Default")
      (node (ref "J6") (pin "P$43") (pinfunction "C13_P$43") (pintype "passive"))
    )
    (net (code "118") (name "unconnected-(J6-C14-PadP$44)") (class "Default")
      (node (ref "J6") (pin "P$44") (pinfunction "C14_P$44") (pintype "passive"))
    )
    (net (code "119") (name "unconnected-(J6-C23-PadP$53)") (class "Default")
      (node (ref "J6") (pin "P$53") (pinfunction "C23_P$53") (pintype "passive"))
    )
    (net (code "120") (name "unconnected-(J6-D12-PadP$12)") (class "Default")
      (node (ref "J6") (pin "P$12") (pinfunction "D12_P$12") (pintype "passive"))
    )
    (net (code "121") (name "unconnected-(J6-D13-PadP$13)") (class "Default")
      (node (ref "J6") (pin "P$13") (pinfunction "D13_P$13") (pintype "passive"))
    )
    (net (code "122") (name "unconnected-(J6-D14-PadP$14)") (class "Default")
      (node (ref "J6") (pin "P$14") (pinfunction "D14_P$14") (pintype "passive"))
    )
    (net (code "123") (name "unconnected-(J6-D23-PadP$23)") (class "Default")
      (node (ref "J6") (pin "P$23") (pinfunction "D23_P$23") (pintype "passive"))
    )
  )
)
